# Clock.net
KiCad netlist of a schematic drawn in EAGLE
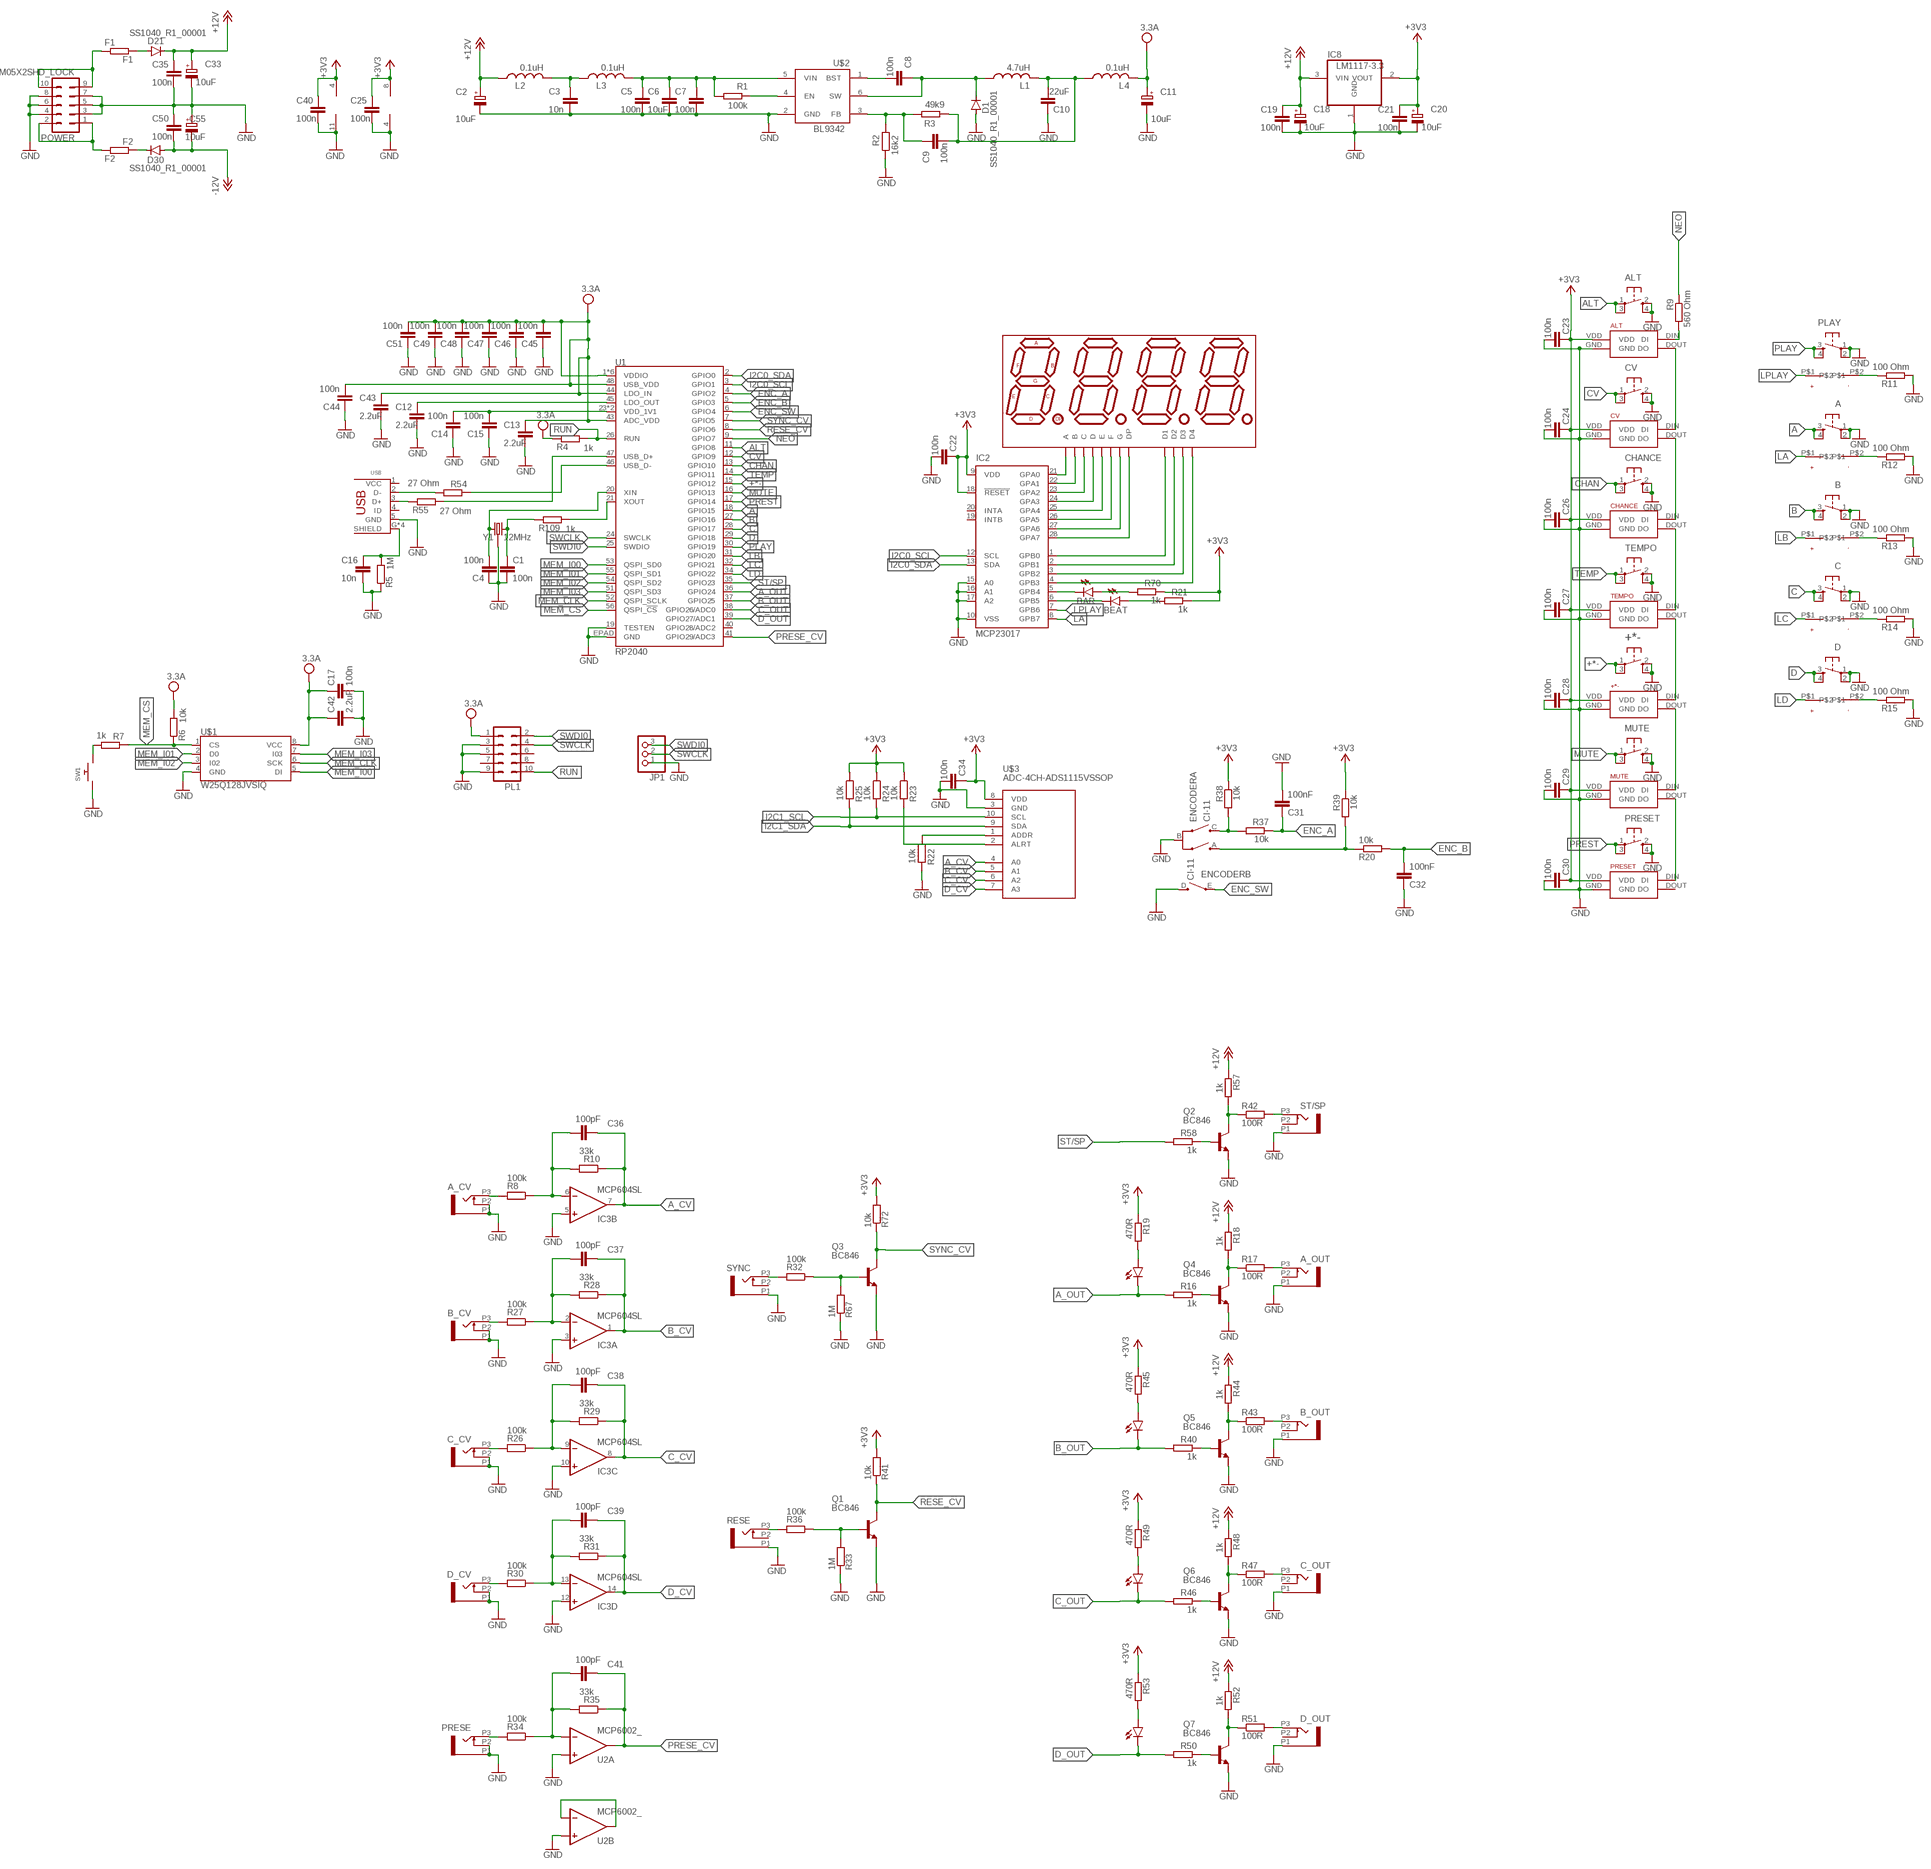
[diagram p0: schematic, sheet 1]

(export (version "E")
  (design (tool "Eeschema 10.0.6"))
  (components
    (comp (ref "+*-")
      (value "BUTTON_NEOPIXEL")
      (footprint "eagle-import:BUTTON_PIXEL")
      (libsource (lib "eagle-import") (part "BUTTON_NEOPIXEL"))
    )
    (comp (ref "A")
      (value "DTS-6_LEDTME")
      (footprint "eagle-import:TMEBUTTON")
      (libsource (lib "eagle-import") (part "DTS-6_LEDTME"))
    )
    (comp (ref "ALT")
      (value "BUTTON_NEOPIXEL")
      (footprint "eagle-import:BUTTON_PIXEL")
      (libsource (lib "eagle-import") (part "BUTTON_NEOPIXEL"))
    )
    (comp (ref "A_CV")
      (value "OG-PJ301_PJ301_THONKICONNNOHOLER")
      (footprint "eagle-import:NOHOLER_GND_SHORT_PADMINI_GND")
      (libsource (lib "eagle-import") (part "OG-PJ301_PJ301_THONKICONNNOHOLER_GND_SHORT_PADMINI_GND"))
    )
    (comp (ref "A_OUT")
      (value "OG-PJ301_PJ301_THONKICONNNOHOLER")
      (footprint "eagle-import:NOHOLER_GND_SHORT_PADMINI_GND")
      (libsource (lib "eagle-import") (part "OG-PJ301_PJ301_THONKICONNNOHOLER_GND_SHORT_PADMINI_GND"))
    )
    (comp (ref "B")
      (value "DTS-6_LEDTME")
      (footprint "eagle-import:TMEBUTTON")
      (libsource (lib "eagle-import") (part "DTS-6_LEDTME"))
    )
    (comp (ref "BAR")
      (value "2 MM LED")
      (footprint "eagle-import:LED3MM")
      (libsource (lib "eagle-import") (part "LED3MM"))
    )
    (comp (ref "BEAT")
      (value "2 MM LED")
      (footprint "eagle-import:LED3MM")
      (libsource (lib "eagle-import") (part "LED3MM"))
    )
    (comp (ref "B_CV")
      (value "OG-PJ301_PJ301_THONKICONNNOHOLER")
      (footprint "eagle-import:NOHOLER_GND_SHORT_PADMINI_GND")
      (libsource (lib "eagle-import") (part "OG-PJ301_PJ301_THONKICONNNOHOLER_GND_SHORT_PADMINI_GND"))
    )
    (comp (ref "B_OUT")
      (value "OG-PJ301_PJ301_THONKICONNNOHOLER")
      (footprint "eagle-import:NOHOLER_GND_SHORT_PADMINI_GND")
      (libsource (lib "eagle-import") (part "OG-PJ301_PJ301_THONKICONNNOHOLER_GND_SHORT_PADMINI_GND"))
    )
    (comp (ref "C")
      (value "DTS-6_LEDTME")
      (footprint "eagle-import:TMEBUTTON")
      (libsource (lib "eagle-import") (part "DTS-6_LEDTME"))
    )
    (comp (ref "C1")
      (value "100n")
      (footprint "eagle-import:C0603")
      (libsource (lib "eagle-import") (part "C-EUC0603"))
    )
    (comp (ref "C2")
      (value "10uF")
      (footprint "eagle-import:PANASONIC_B")
      (libsource (lib "eagle-import") (part "CPOL-EUB"))
    )
    (comp (ref "C3")
      (value "10n")
      (footprint "eagle-import:C0603")
      (libsource (lib "eagle-import") (part "C-EUC0603"))
    )
    (comp (ref "C4")
      (value "100n")
      (footprint "eagle-import:C0603")
      (libsource (lib "eagle-import") (part "C-EUC0603"))
    )
    (comp (ref "C5")
      (value "100n")
      (footprint "eagle-import:C0603")
      (libsource (lib "eagle-import") (part "C-EUC0603"))
    )
    (comp (ref "C6")
      (value "10uF")
      (footprint "eagle-import:C0603")
      (libsource (lib "eagle-import") (part "C-EUC0603"))
    )
    (comp (ref "C7")
      (value "100n")
      (footprint "eagle-import:C0603")
      (libsource (lib "eagle-import") (part "C-EUC0603"))
    )
    (comp (ref "C8")
      (value "100n")
      (footprint "eagle-import:C0603")
      (libsource (lib "eagle-import") (part "C-EUC0603"))
    )
    (comp (ref "C9")
      (value "100n")
      (footprint "eagle-import:C0603")
      (libsource (lib "eagle-import") (part "C-EUC0603"))
    )
    (comp (ref "C10")
      (value "22uF")
      (footprint "eagle-import:C0603")
      (libsource (lib "eagle-import") (part "C-EUC0603"))
    )
    (comp (ref "C11")
      (value "10uF")
      (footprint "eagle-import:PANASONIC_B")
      (libsource (lib "eagle-import") (part "CPOL-EUB"))
    )
    (comp (ref "C12")
      (value "2.2uF")
      (footprint "eagle-import:C0603")
      (libsource (lib "eagle-import") (part "C-EUC0603"))
    )
    (comp (ref "C13")
      (value "2.2uF")
      (footprint "eagle-import:C0603")
      (libsource (lib "eagle-import") (part "C-EUC0603"))
    )
    (comp (ref "C14")
      (value "100n")
      (footprint "eagle-import:C0603")
      (libsource (lib "eagle-import") (part "C-EUC0603"))
    )
    (comp (ref "C15")
      (value "100n")
      (footprint "eagle-import:C0603")
      (libsource (lib "eagle-import") (part "C-EUC0603"))
    )
    (comp (ref "C16")
      (value "10n")
      (footprint "eagle-import:C0603")
      (libsource (lib "eagle-import") (part "C-EUC0603"))
    )
    (comp (ref "C17")
      (value "100n")
      (footprint "eagle-import:C0603")
      (libsource (lib "eagle-import") (part "C-EUC0603"))
    )
    (comp (ref "C18")
      (value "10uF")
      (footprint "eagle-import:PANASONIC_B")
      (libsource (lib "eagle-import") (part "CPOL-EUB"))
    )
    (comp (ref "C19")
      (value "100n")
      (footprint "eagle-import:C0603")
      (libsource (lib "eagle-import") (part "C-EUC0603"))
    )
    (comp (ref "C20")
      (value "10uF")
      (footprint "eagle-import:PANASONIC_B")
      (libsource (lib "eagle-import") (part "CPOL-EUB"))
    )
    (comp (ref "C21")
      (value "100n")
      (footprint "eagle-import:C0603")
      (libsource (lib "eagle-import") (part "C-EUC0603"))
    )
    (comp (ref "C22")
      (value "100n")
      (footprint "eagle-import:C0603")
      (libsource (lib "eagle-import") (part "C-EUC0603"))
    )
    (comp (ref "C23")
      (value "100n")
      (footprint "eagle-import:C0603")
      (libsource (lib "eagle-import") (part "C-EUC0603"))
    )
    (comp (ref "C24")
      (value "100n")
      (footprint "eagle-import:C0603")
      (libsource (lib "eagle-import") (part "C-EUC0603"))
    )
    (comp (ref "C25")
      (value "100n")
      (footprint "eagle-import:C0603")
      (libsource (lib "eagle-import") (part "C-EUC0603"))
    )
    (comp (ref "C26")
      (value "100n")
      (footprint "eagle-import:C0603")
      (libsource (lib "eagle-import") (part "C-EUC0603"))
    )
    (comp (ref "C27")
      (value "100n")
      (footprint "eagle-import:C0603")
      (libsource (lib "eagle-import") (part "C-EUC0603"))
    )
    (comp (ref "C28")
      (value "100n")
      (footprint "eagle-import:C0603")
      (libsource (lib "eagle-import") (part "C-EUC0603"))
    )
    (comp (ref "C29")
      (value "100n")
      (footprint "eagle-import:C0603")
      (libsource (lib "eagle-import") (part "C-EUC0603"))
    )
    (comp (ref "C30")
      (value "100n")
      (footprint "eagle-import:C0603")
      (libsource (lib "eagle-import") (part "C-EUC0603"))
    )
    (comp (ref "C31")
      (value "100nF")
      (footprint "eagle-import:C0603")
      (libsource (lib "eagle-import") (part "rcl_334_C-EUC0603"))
    )
    (comp (ref "C32")
      (value "100nF")
      (footprint "eagle-import:C0603")
      (libsource (lib "eagle-import") (part "rcl_334_C-EUC0603"))
    )
    (comp (ref "C33")
      (value "10uF")
      (footprint "eagle-import:PANASONIC_B")
      (libsource (lib "eagle-import") (part "CPOL-EUB"))
    )
    (comp (ref "C34")
      (value "100n")
      (footprint "eagle-import:C0603")
      (libsource (lib "eagle-import") (part "C-EUC0603"))
    )
    (comp (ref "C35")
      (value "100n")
      (footprint "eagle-import:C0603")
      (libsource (lib "eagle-import") (part "C-EUC0603"))
    )
    (comp (ref "C36")
      (value "100pF")
      (footprint "eagle-import:C0603")
      (libsource (lib "eagle-import") (part "rcl_334_C-EUC0603"))
    )
    (comp (ref "C37")
      (value "100pF")
      (footprint "eagle-import:C0603")
      (libsource (lib "eagle-import") (part "rcl_334_C-EUC0603"))
    )
    (comp (ref "C38")
      (value "100pF")
      (footprint "eagle-import:C0603")
      (libsource (lib "eagle-import") (part "rcl_334_C-EUC0603"))
    )
    (comp (ref "C39")
      (value "100pF")
      (footprint "eagle-import:C0603")
      (libsource (lib "eagle-import") (part "rcl_334_C-EUC0603"))
    )
    (comp (ref "C40")
      (value "100n")
      (footprint "eagle-import:C0603")
      (libsource (lib "eagle-import") (part "C-EUC0603"))
    )
    (comp (ref "C41")
      (value "100pF")
      (footprint "eagle-import:C0603")
      (libsource (lib "eagle-import") (part "rcl_334_C-EUC0603"))
    )
    (comp (ref "C42")
      (value "2.2uF")
      (footprint "eagle-import:C0603")
      (libsource (lib "eagle-import") (part "C-EUC0603"))
    )
    (comp (ref "C43")
      (value "2.2uF")
      (footprint "eagle-import:C0603")
      (libsource (lib "eagle-import") (part "C-EUC0603"))
    )
    (comp (ref "C44")
      (value "100n")
      (footprint "eagle-import:C0603")
      (libsource (lib "eagle-import") (part "C-EUC0603"))
    )
    (comp (ref "C45")
      (value "100n")
      (footprint "eagle-import:C0603")
      (libsource (lib "eagle-import") (part "C-EUC0603"))
    )
    (comp (ref "C46")
      (value "100n")
      (footprint "eagle-import:C0603")
      (libsource (lib "eagle-import") (part "C-EUC0603"))
    )
    (comp (ref "C47")
      (value "100n")
      (footprint "eagle-import:C0603")
      (libsource (lib "eagle-import") (part "C-EUC0603"))
    )
    (comp (ref "C48")
      (value "100n")
      (footprint "eagle-import:C0603")
      (libsource (lib "eagle-import") (part "C-EUC0603"))
    )
    (comp (ref "C49")
      (value "100n")
      (footprint "eagle-import:C0603")
      (libsource (lib "eagle-import") (part "C-EUC0603"))
    )
    (comp (ref "C50")
      (value "100n")
      (footprint "eagle-import:C0603")
      (libsource (lib "eagle-import") (part "C-EUC0603"))
    )
    (comp (ref "C51")
      (value "100n")
      (footprint "eagle-import:C0603")
      (libsource (lib "eagle-import") (part "C-EUC0603"))
    )
    (comp (ref "C55")
      (value "10uF")
      (footprint "eagle-import:PANASONIC_B")
      (libsource (lib "eagle-import") (part "CPOL-EUB"))
    )
    (comp (ref "CHANCE")
      (value "BUTTON_NEOPIXEL")
      (footprint "eagle-import:BUTTON_PIXEL")
      (libsource (lib "eagle-import") (part "BUTTON_NEOPIXEL"))
    )
    (comp (ref "CV")
      (value "BUTTON_NEOPIXEL")
      (footprint "eagle-import:BUTTON_PIXEL")
      (libsource (lib "eagle-import") (part "BUTTON_NEOPIXEL"))
    )
    (comp (ref "C_CV")
      (value "OG-PJ301_PJ301_THONKICONNNOHOLER")
      (footprint "eagle-import:NOHOLER_GND_SHORT_PADMINI_GND")
      (libsource (lib "eagle-import") (part "OG-PJ301_PJ301_THONKICONNNOHOLER_GND_SHORT_PADMINI_GND"))
    )
    (comp (ref "C_OUT")
      (value "OG-PJ301_PJ301_THONKICONNNOHOLER")
      (footprint "eagle-import:NOHOLER_GND_SHORT_PADMINI_GND")
      (libsource (lib "eagle-import") (part "OG-PJ301_PJ301_THONKICONNNOHOLER_GND_SHORT_PADMINI_GND"))
    )
    (comp (ref "D")
      (value "DTS-6_LEDTME")
      (footprint "eagle-import:TMEBUTTON")
      (libsource (lib "eagle-import") (part "DTS-6_LEDTME"))
    )
    (comp (ref "D1")
      (value "SS1040_R1_00001")
      (footprint "eagle-import:SOD123")
      (libsource (lib "eagle-import") (part "DIODE-SOD123"))
    )
    (comp (ref "D21")
      (value "SS1040_R1_00001")
      (footprint "eagle-import:SOD123")
      (libsource (lib "eagle-import") (part "DIODE-SOD123"))
    )
    (comp (ref "D30")
      (value "SS1040_R1_00001")
      (footprint "eagle-import:SOD123")
      (libsource (lib "eagle-import") (part "DIODE-SOD123"))
    )
    (comp (ref "D_CV")
      (value "OG-PJ301_PJ301_THONKICONNNOHOLER")
      (footprint "eagle-import:NOHOLER_GND_SHORT_PADMINI_GND")
      (libsource (lib "eagle-import") (part "OG-PJ301_PJ301_THONKICONNNOHOLER_GND_SHORT_PADMINI_GND"))
    )
    (comp (ref "D_OUT")
      (value "OG-PJ301_PJ301_THONKICONNNOHOLER")
      (footprint "eagle-import:NOHOLER_GND_SHORT_PADMINI_GND")
      (libsource (lib "eagle-import") (part "OG-PJ301_PJ301_THONKICONNNOHOLER_GND_SHORT_PADMINI_GND"))
    )
    (comp (ref "ENCODER")
      (value "CI-11")
      (footprint "eagle-import:CI-11")
      (libsource (lib "eagle-import") (part "CI-11"))
    )
    (comp (ref "F1")
      (value "F1")
      (footprint "eagle-import:R0603")
      (libsource (lib "eagle-import") (part "R-EU_R0603"))
    )
    (comp (ref "F2")
      (value "F2")
      (footprint "eagle-import:R0603")
      (libsource (lib "eagle-import") (part "R-EU_R0603"))
    )
    (comp (ref "IC2")
      (value "MCP23017")
      (footprint "eagle-import:SO28")
      (libsource (lib "eagle-import") (part "MCP23017"))
    )
    (comp (ref "IC3")
      (value "MCP604SL")
      (footprint "eagle-import:SO14")
      (libsource (lib "eagle-import") (part "MCP604SL"))
    )
    (comp (ref "IC8")
      (value "LM1117-3.3")
      (footprint "eagle-import:SOT223")
      (libsource (lib "eagle-import") (part "REG1117"))
    )
    (comp (ref "JP1")
      (value "PINHD-1X31X3*")
      (footprint "eagle-import:1X3_")
      (libsource (lib "eagle-import") (part "PINHD-1X31X3"))
    )
    (comp (ref "L1")
      (value "4.7uH")
      (footprint "eagle-import:L3225P")
      (libsource (lib "eagle-import") (part "L-USL3225P"))
    )
    (comp (ref "L2")
      (value "0.1uH")
      (footprint "eagle-import:L3225P")
      (libsource (lib "eagle-import") (part "L-USL3225P"))
    )
    (comp (ref "L3")
      (value "0.1uH")
      (footprint "eagle-import:L3225P")
      (libsource (lib "eagle-import") (part "L-USL3225P"))
    )
    (comp (ref "L4")
      (value "0.1uH")
      (footprint "eagle-import:L3225P")
      (libsource (lib "eagle-import") (part "L-USL3225P"))
    )
    (comp (ref "LED_A_OUT")
      (value "2 MM LED")
      (footprint "eagle-import:LED3MM")
      (libsource (lib "eagle-import") (part "LED3MM"))
    )
    (comp (ref "LED_B_OUT")
      (value "2 MM LED")
      (footprint "eagle-import:LED3MM")
      (libsource (lib "eagle-import") (part "LED3MM"))
    )
    (comp (ref "LED_C_OUT")
      (value "2 MM LED")
      (footprint "eagle-import:LED3MM")
      (libsource (lib "eagle-import") (part "LED3MM"))
    )
    (comp (ref "LED_D_OUT")
      (value "2 MM LED")
      (footprint "eagle-import:LED3MM")
      (libsource (lib "eagle-import") (part "LED3MM"))
    )
    (comp (ref "LFD36BUE-101B")
      (value "7-SEGMENT-4DIGIT-20MM")
      (footprint "eagle-import:7-SEGMENT-4DIGIT-30MM")
      (libsource (lib "eagle-import") (part "7-SEGMENT-4DIGIT-20MM"))
    )
    (comp (ref "MUTE")
      (value "BUTTON_NEOPIXEL")
      (footprint "eagle-import:BUTTON_PIXEL")
      (libsource (lib "eagle-import") (part "BUTTON_NEOPIXEL"))
    )
    (comp (ref "PL1")
      (value "2X5-1241050")
      (footprint "eagle-import:AMP-1241050-5")
      (libsource (lib "eagle-import") (part "2X5-1241050"))
    )
    (comp (ref "PLAY")
      (value "DTS-6_LEDTME")
      (footprint "eagle-import:TMEBUTTON")
      (libsource (lib "eagle-import") (part "DTS-6_LEDTME"))
    )
    (comp (ref "POWER")
      (value "M05X2SHD_LOCK")
      (footprint "eagle-import:2X5-SHROUDED_LOCK")
      (libsource (lib "eagle-import") (part "M05X2SHD_LOCK"))
    )
    (comp (ref "PRESE")
      (value "OG-PJ301_PJ301_THONKICONNNOHOLER")
      (footprint "eagle-import:NOHOLER_GND_SHORT_PADMINI_GND")
      (libsource (lib "eagle-import") (part "OG-PJ301_PJ301_THONKICONNNOHOLER_GND_SHORT_PADMINI_GND"))
    )
    (comp (ref "PRESET")
      (value "BUTTON_NEOPIXEL")
      (footprint "eagle-import:BUTTON_PIXEL")
      (libsource (lib "eagle-import") (part "BUTTON_NEOPIXEL"))
    )
    (comp (ref "Q1")
      (value "BC846")
      (footprint "eagle-import:SOT23")
      (libsource (lib "eagle-import") (part "BC846"))
    )
    (comp (ref "Q2")
      (value "BC846")
      (footprint "eagle-import:SOT23")
      (libsource (lib "eagle-import") (part "BC846"))
    )
    (comp (ref "Q3")
      (value "BC846")
      (footprint "eagle-import:SOT23")
      (libsource (lib "eagle-import") (part "BC846"))
    )
    (comp (ref "Q4")
      (value "BC846")
      (footprint "eagle-import:SOT23")
      (libsource (lib "eagle-import") (part "BC846"))
    )
    (comp (ref "Q5")
      (value "BC846")
      (footprint "eagle-import:SOT23")
      (libsource (lib "eagle-import") (part "BC846"))
    )
    (comp (ref "Q6")
      (value "BC846")
      (footprint "eagle-import:SOT23")
      (libsource (lib "eagle-import") (part "BC846"))
    )
    (comp (ref "Q7")
      (value "BC846")
      (footprint "eagle-import:SOT23")
      (libsource (lib "eagle-import") (part "BC846"))
    )
    (comp (ref "R1")
      (value "100k")
      (footprint "eagle-import:R0603")
      (libsource (lib "eagle-import") (part "R-EU_R0603"))
    )
    (comp (ref "R2")
      (value "16k2")
      (footprint "eagle-import:R0603")
      (libsource (lib "eagle-import") (part "R-EU_R0603"))
    )
    (comp (ref "R3")
      (value "49k9")
      (footprint "eagle-import:R0603")
      (libsource (lib "eagle-import") (part "R-EU_R0603"))
    )
    (comp (ref "R4")
      (value "1k")
      (footprint "eagle-import:R0603")
      (libsource (lib "eagle-import") (part "R-EU_R0603"))
    )
    (comp (ref "R5")
      (value "1M")
      (footprint "eagle-import:R0603")
      (libsource (lib "eagle-import") (part "R-EU_R0603"))
    )
    (comp (ref "R6")
      (value "10k")
      (footprint "eagle-import:R0603")
      (libsource (lib "eagle-import") (part "R-EU_R0603"))
    )
    (comp (ref "R7")
      (value "1k")
      (footprint "eagle-import:R0603")
      (libsource (lib "eagle-import") (part "R-EU_R0603"))
    )
    (comp (ref "R8")
      (value "100k")
      (footprint "eagle-import:R0603")
      (libsource (lib "eagle-import") (part "R-EU_R0603"))
    )
    (comp (ref "R9")
      (value "560 Ohm")
      (footprint "eagle-import:R0603")
      (libsource (lib "eagle-import") (part "R-EU_R0603"))
    )
    (comp (ref "R10")
      (value "33k")
      (footprint "eagle-import:R0603")
      (libsource (lib "eagle-import") (part "R-EU_R0603"))
    )
    (comp (ref "R11")
      (value "100 Ohm")
      (footprint "eagle-import:R0603")
      (libsource (lib "eagle-import") (part "R-EU_R0603"))
    )
    (comp (ref "R12")
      (value "100 Ohm")
      (footprint "eagle-import:R0603")
      (libsource (lib "eagle-import") (part "R-EU_R0603"))
    )
    (comp (ref "R13")
      (value "100 Ohm")
      (footprint "eagle-import:R0603")
      (libsource (lib "eagle-import") (part "R-EU_R0603"))
    )
    (comp (ref "R14")
      (value "100 Ohm")
      (footprint "eagle-import:R0603")
      (libsource (lib "eagle-import") (part "R-EU_R0603"))
    )
    (comp (ref "R15")
      (value "100 Ohm")
      (footprint "eagle-import:R0603")
      (libsource (lib "eagle-import") (part "R-EU_R0603"))
    )
    (comp (ref "R16")
      (value "1k")
      (footprint "eagle-import:R0603")
      (libsource (lib "eagle-import") (part "R-EU_R0603"))
    )
    (comp (ref "R17")
      (value "100R")
      (footprint "eagle-import:R0603")
      (libsource (lib "eagle-import") (part "R-EU_R0603"))
    )
    (comp (ref "R18")
      (value "1k")
      (footprint "eagle-import:R0603")
      (libsource (lib "eagle-import") (part "R-EU_R0603"))
    )
    (comp (ref "R19")
      (value "470R")
      (footprint "eagle-import:R0603")
      (libsource (lib "eagle-import") (part "R-EU_R0603"))
    )
    (comp (ref "R20")
      (value "10k")
      (footprint "eagle-import:R0603")
      (libsource (lib "eagle-import") (part "rcl_334_R-EU_R0603"))
    )
    (comp (ref "R21")
      (value "1k")
      (footprint "eagle-import:R0603")
      (libsource (lib "eagle-import") (part "R-EU_R0603"))
    )
    (comp (ref "R22")
      (value "10k")
      (footprint "eagle-import:R0603")
      (libsource (lib "eagle-import") (part "R-EU_R0603"))
    )
    (comp (ref "R23")
      (value "10k")
      (footprint "eagle-import:R0603")
      (libsource (lib "eagle-import") (part "R-EU_R0603"))
    )
    (comp (ref "R24")
      (value "10k")
      (footprint "eagle-import:R0603")
      (libsource (lib "eagle-import") (part "R-EU_R0603"))
    )
    (comp (ref "R25")
      (value "10k")
      (footprint "eagle-import:R0603")
      (libsource (lib "eagle-import") (part "R-EU_R0603"))
    )
    (comp (ref "R26")
      (value "100k")
      (footprint "eagle-import:R0603")
      (libsource (lib "eagle-import") (part "R-EU_R0603"))
    )
    (comp (ref "R27")
      (value "100k")
      (footprint "eagle-import:R0603")
      (libsource (lib "eagle-import") (part "R-EU_R0603"))
    )
    (comp (ref "R28")
      (value "33k")
      (footprint "eagle-import:R0603")
      (libsource (lib "eagle-import") (part "R-EU_R0603"))
    )
    (comp (ref "R29")
      (value "33k")
      (footprint "eagle-import:R0603")
      (libsource (lib "eagle-import") (part "R-EU_R0603"))
    )
    (comp (ref "R30")
      (value "100k")
      (footprint "eagle-import:R0603")
      (libsource (lib "eagle-import") (part "R-EU_R0603"))
    )
    (comp (ref "R31")
      (value "33k")
      (footprint "eagle-import:R0603")
      (libsource (lib "eagle-import") (part "R-EU_R0603"))
    )
    (comp (ref "R32")
      (value "100k")
      (footprint "eagle-import:R0603")
      (libsource (lib "eagle-import") (part "R-EU_R0603"))
    )
    (comp (ref "R33")
      (value "1M")
      (footprint "eagle-import:R0603")
      (libsource (lib "eagle-import") (part "R-EU_R0603"))
    )
    (comp (ref "R34")
      (value "100k")
      (footprint "eagle-import:R0603")
      (libsource (lib "eagle-import") (part "R-EU_R0603"))
    )
    (comp (ref "R35")
      (value "33k")
      (footprint "eagle-import:R0603")
      (libsource (lib "eagle-import") (part "R-EU_R0603"))
    )
    (comp (ref "R36")
      (value "100k")
      (footprint "eagle-import:R0603")
      (libsource (lib "eagle-import") (part "R-EU_R0603"))
    )
    (comp (ref "R37")
      (value "10k")
      (footprint "eagle-import:R0603")
      (libsource (lib "eagle-import") (part "rcl_334_R-EU_R0603"))
    )
    (comp (ref "R38")
      (value "10k")
      (footprint "eagle-import:R0603")
      (libsource (lib "eagle-import") (part "rcl_334_R-EU_R0603"))
    )
    (comp (ref "R39")
      (value "10k")
      (footprint "eagle-import:R0603")
      (libsource (lib "eagle-import") (part "rcl_334_R-EU_R0603"))
    )
    (comp (ref "R40")
      (value "1k")
      (footprint "eagle-import:R0603")
      (libsource (lib "eagle-import") (part "R-EU_R0603"))
    )
    (comp (ref "R41")
      (value "10k")
      (footprint "eagle-import:R0603")
      (libsource (lib "eagle-import") (part "R-EU_R0603"))
    )
    (comp (ref "R42")
      (value "100R")
      (footprint "eagle-import:R0603")
      (libsource (lib "eagle-import") (part "R-EU_R0603"))
    )
    (comp (ref "R43")
      (value "100R")
      (footprint "eagle-import:R0603")
      (libsource (lib "eagle-import") (part "R-EU_R0603"))
    )
    (comp (ref "R44")
      (value "1k")
      (footprint "eagle-import:R0603")
      (libsource (lib "eagle-import") (part "R-EU_R0603"))
    )
    (comp (ref "R45")
      (value "470R")
      (footprint "eagle-import:R0603")
      (libsource (lib "eagle-import") (part "R-EU_R0603"))
    )
    (comp (ref "R46")
      (value "1k")
      (footprint "eagle-import:R0603")
      (libsource (lib "eagle-import") (part "R-EU_R0603"))
    )
    (comp (ref "R47")
      (value "100R")
      (footprint "eagle-import:R0603")
      (libsource (lib "eagle-import") (part "R-EU_R0603"))
    )
    (comp (ref "R48")
      (value "1k")
      (footprint "eagle-import:R0603")
      (libsource (lib "eagle-import") (part "R-EU_R0603"))
    )
    (comp (ref "R49")
      (value "470R")
      (footprint "eagle-import:R0603")
      (libsource (lib "eagle-import") (part "R-EU_R0603"))
    )
    (comp (ref "R50")
      (value "1k")
      (footprint "eagle-import:R0603")
      (libsource (lib "eagle-import") (part "R-EU_R0603"))
    )
    (comp (ref "R51")
      (value "100R")
      (footprint "eagle-import:R0603")
      (libsource (lib "eagle-import") (part "R-EU_R0603"))
    )
    (comp (ref "R52")
      (value "1k")
      (footprint "eagle-import:R0603")
      (libsource (lib "eagle-import") (part "R-EU_R0603"))
    )
    (comp (ref "R53")
      (value "470R")
      (footprint "eagle-import:R0603")
      (libsource (lib "eagle-import") (part "R-EU_R0603"))
    )
    (comp (ref "R54")
      (value "27 Ohm")
      (footprint "eagle-import:R0603")
      (libsource (lib "eagle-import") (part "R-EU_R0603"))
    )
    (comp (ref "R55")
      (value "27 Ohm")
      (footprint "eagle-import:R0603")
      (libsource (lib "eagle-import") (part "R-EU_R0603"))
    )
    (comp (ref "R57")
      (value "1k")
      (footprint "eagle-import:R0603")
      (libsource (lib "eagle-import") (part "R-EU_R0603"))
    )
    (comp (ref "R58")
      (value "1k")
      (footprint "eagle-import:R0603")
      (libsource (lib "eagle-import") (part "R-EU_R0603"))
    )
    (comp (ref "R67")
      (value "1M")
      (footprint "eagle-import:R0603")
      (libsource (lib "eagle-import") (part "R-EU_R0603"))
    )
    (comp (ref "R70")
      (value "1k")
      (footprint "eagle-import:R0603")
      (libsource (lib "eagle-import") (part "R-EU_R0603"))
    )
    (comp (ref "R72")
      (value "10k")
      (footprint "eagle-import:R0603")
      (libsource (lib "eagle-import") (part "R-EU_R0603"))
    )
    (comp (ref "R109")
      (value "1k")
      (footprint "eagle-import:R0603")
      (libsource (lib "eagle-import") (part "R-EU_R0603"))
    )
    (comp (ref "RESE")
      (value "OG-PJ301_PJ301_THONKICONNNOHOLER")
      (footprint "eagle-import:NOHOLER_GND_SHORT_PADMINI_GND")
      (libsource (lib "eagle-import") (part "OG-PJ301_PJ301_THONKICONNNOHOLER_GND_SHORT_PADMINI_GND"))
    )
    (comp (ref "ST/SP")
      (value "OG-PJ301_PJ301_THONKICONNNOHOLER")
      (footprint "eagle-import:NOHOLER_GND_SHORT_PADMINI_GND")
      (libsource (lib "eagle-import") (part "OG-PJ301_PJ301_THONKICONNNOHOLER_GND_SHORT_PADMINI_GND"))
    )
    (comp (ref "SW1")
      (value "SWITCH_PUSHBUTTONSOFTTOUCHSMD_SJ")
      (footprint "eagle-import:PUSHBUTTON_SMD_SJ")
      (libsource (lib "eagle-import") (part "SWITCH_PUSHBUTTONSOFTTOUCHSMD_SJ"))
    )
    (comp (ref "SYNC")
      (value "OG-PJ301_PJ301_THONKICONNNOHOLER")
      (footprint "eagle-import:NOHOLER_GND_SHORT_PADMINI_GND")
      (libsource (lib "eagle-import") (part "OG-PJ301_PJ301_THONKICONNNOHOLER_GND_SHORT_PADMINI_GND"))
    )
    (comp (ref "TEMPO")
      (value "BUTTON_NEOPIXEL")
      (footprint "eagle-import:BUTTON_PIXEL")
      (libsource (lib "eagle-import") (part "BUTTON_NEOPIXEL"))
    )
    (comp (ref "U$1")
      (value "W25Q128JVSIQ")
      (footprint "eagle-import:SOIC-8")
      (libsource (lib "eagle-import") (part "W25Q128JVSIQ"))
    )
    (comp (ref "U$2")
      (value "BL9342")
      (footprint "eagle-import:SOT23-6")
      (libsource (lib "eagle-import") (part "BL9342"))
    )
    (comp (ref "U$3")
      (value "ADC-4CH-ADS1115VSSOP")
      (footprint "eagle-import:ADC-4CH-ADS1115-VSSOP")
      (libsource (lib "eagle-import") (part "ADC-4CH-ADS1115VSSOP"))
    )
    (comp (ref "U1")
      (value "RP2040")
      (footprint "eagle-import:QFN-56")
      (libsource (lib "eagle-import") (part "RP2040"))
    )
    (comp (ref "U2")
      (value "MCP6002_")
      (footprint "eagle-import:SO08")
      (libsource (lib "eagle-import") (part "MCP6002_"))
    )
    (comp (ref "USB")
      (value "USB_HRS_ZX62-B-5PA(11)MICRO.B")
      (footprint "eagle-import:HRS_ZX62RD-AB-5P8")
      (libsource (lib "eagle-import") (part "USB_HRS_ZX62-B-5PA(11)MICRO.B"))
    )
    (comp (ref "Y1")
      (value "12MHz")
      (footprint "eagle-import:CRYSTAL-SMD-2.0X1.6MM-WE")
      (libsource (lib "eagle-import") (part "CRYSTAL-25MHZ-WE-SMD-2.0X1.6MM-WE"))
    )
  )
  (nets
    (net (code "1") (name "+*-") (class "Default")
      (node (ref "+*-") (pin "1") (pinfunction "1_1") (pintype "passive"))
      (node (ref "+*-") (pin "3") (pinfunction "3_3") (pintype "passive"))
      (node (ref "U1") (pin "15") (pinfunction "GPIO12_15") (pintype "bidirectional"))
    )
    (net (code "2") (name "+3V3") (class "Default")
      (node (ref "+*-") (pin "VDD") (pinfunction "VDD_VDD") (pintype "bidirectional"))
      (node (ref "ALT") (pin "VDD") (pinfunction "VDD_VDD") (pintype "bidirectional"))
      (node (ref "C20") (pin "+") (pinfunction "+_+") (pintype "passive"))
      (node (ref "C21") (pin "1") (pinfunction "1_1") (pintype "passive"))
      (node (ref "C22") (pin "1") (pinfunction "1_1") (pintype "passive"))
      (node (ref "C23") (pin "1") (pinfunction "1_1") (pintype "passive"))
      (node (ref "C24") (pin "1") (pinfunction "1_1") (pintype "passive"))
      (node (ref "C25") (pin "1") (pinfunction "1_1") (pintype "passive"))
      (node (ref "C26") (pin "1") (pinfunction "1_1") (pintype "passive"))
      (node (ref "C27") (pin "1") (pinfunction "1_1") (pintype "passive"))
      (node (ref "C28") (pin "1") (pinfunction "1_1") (pintype "passive"))
      (node (ref "C29") (pin "1") (pinfunction "1_1") (pintype "passive"))
      (node (ref "C30") (pin "1") (pinfunction "1_1") (pintype "passive"))
      (node (ref "C34") (pin "1") (pinfunction "1_1") (pintype "passive"))
      (node (ref "C40") (pin "1") (pinfunction "1_1") (pintype "passive"))
      (node (ref "CHANCE") (pin "VDD") (pinfunction "VDD_VDD") (pintype "bidirectional"))
      (node (ref "CV") (pin "VDD") (pinfunction "VDD_VDD") (pintype "bidirectional"))
      (node (ref "IC2") (pin "18") (pinfunction "~{RESET}_18") (pintype "input"))
      (node (ref "IC2") (pin "9") (pinfunction "VDD_9") (pintype "power_in"))
      (node (ref "IC3") (pin "4") (pinfunction "V+_4") (pintype "power_in"))
      (node (ref "IC8") (pin "2") (pinfunction "VOUT_2") (pintype "output"))
      (node (ref "MUTE") (pin "VDD") (pinfunction "VDD_VDD") (pintype "bidirectional"))
      (node (ref "PRESET") (pin "VDD") (pinfunction "VDD_VDD") (pintype "bidirectional"))
      (node (ref "R19") (pin "1") (pinfunction "1_1") (pintype "passive"))
      (node (ref "R21") (pin "1") (pinfunction "1_1") (pintype "passive"))
      (node (ref "R23") (pin "1") (pinfunction "1_1") (pintype "passive"))
      (node (ref "R24") (pin "1") (pinfunction "1_1") (pintype "passive"))
      (node (ref "R25") (pin "1") (pinfunction "1_1") (pintype "passive"))
      (node (ref "R38") (pin "1") (pinfunction "1_1") (pintype "passive"))
      (node (ref "R39") (pin "1") (pinfunction "1_1") (pintype "passive"))
      (node (ref "R41") (pin "2") (pinfunction "2_2") (pintype "passive"))
      (node (ref "R45") (pin "1") (pinfunction "1_1") (pintype "passive"))
      (node (ref "R49") (pin "1") (pinfunction "1_1") (pintype "passive"))
      (node (ref "R53") (pin "1") (pinfunction "1_1") (pintype "passive"))
      (node (ref "R70") (pin "1") (pinfunction "1_1") (pintype "passive"))
      (node (ref "R72") (pin "2") (pinfunction "2_2") (pintype "passive"))
      (node (ref "TEMPO") (pin "VDD") (pinfunction "VDD_VDD") (pintype "bidirectional"))
      (node (ref "U$3") (pin "8") (pinfunction "VDD_8") (pintype "power_in"))
      (node (ref "U2") (pin "8") (pinfunction "V+_8") (pintype "power_in"))
    )
    (net (code "3") (name "+12V") (class "Default")
      (node (ref "C18") (pin "+") (pinfunction "+_+") (pintype "passive"))
      (node (ref "C19") (pin "1") (pinfunction "1_1") (pintype "passive"))
      (node (ref "C2") (pin "+") (pinfunction "+_+") (pintype "passive"))
      (node (ref "C33") (pin "+") (pinfunction "+_+") (pintype "passive"))
      (node (ref "C35") (pin "1") (pinfunction "1_1") (pintype "passive"))
      (node (ref "D21") (pin "C") (pinfunction "C_C") (pintype "passive"))
      (node (ref "IC8") (pin "3") (pinfunction "VIN_3") (pintype "input"))
      (node (ref "L2") (pin "1") (pinfunction "1_1") (pintype "passive"))
      (node (ref "R18") (pin "1") (pinfunction "1_1") (pintype "passive"))
      (node (ref "R44") (pin "1") (pinfunction "1_1") (pintype "passive"))
      (node (ref "R48") (pin "1") (pinfunction "1_1") (pintype "passive"))
      (node (ref "R52") (pin "1") (pinfunction "1_1") (pintype "passive"))
      (node (ref "R57") (pin "1") (pinfunction "1_1") (pintype "passive"))
    )
    (net (code "4") (name "-12V") (class "Default")
      (node (ref "C50") (pin "2") (pinfunction "2_2") (pintype "passive"))
      (node (ref "C55") (pin "-") (pinfunction "-_-") (pintype "passive"))
      (node (ref "D30") (pin "A") (pinfunction "A_A") (pintype "passive"))
    )
    (net (code "5") (name "3.3A") (class "Default")
      (node (ref "C11") (pin "+") (pinfunction "+_+") (pintype "passive"))
      (node (ref "C13") (pin "1") (pinfunction "1_1") (pintype "passive"))
      (node (ref "C17") (pin "1") (pinfunction "1_1") (pintype "passive"))
      (node (ref "C42") (pin "1") (pinfunction "1_1") (pintype "passive"))
      (node (ref "C43") (pin "1") (pinfunction "1_1") (pintype "passive"))
      (node (ref "C44") (pin "2") (pinfunction "2_2") (pintype "passive"))
      (node (ref "C45") (pin "2") (pinfunction "2_2") (pintype "passive"))
      (node (ref "C46") (pin "2") (pinfunction "2_2") (pintype "passive"))
      (node (ref "C47") (pin "2") (pinfunction "2_2") (pintype "passive"))
      (node (ref "C48") (pin "2") (pinfunction "2_2") (pintype "passive"))
      (node (ref "C49") (pin "2") (pinfunction "2_2") (pintype "passive"))
      (node (ref "C51") (pin "2") (pinfunction "2_2") (pintype "passive"))
      (node (ref "L4") (pin "2") (pinfunction "2_2") (pintype "passive"))
      (node (ref "PL1") (pin "1") (pinfunction "1_1") (pintype "passive"))
      (node (ref "R4") (pin "1") (pinfunction "1_1") (pintype "passive"))
      (node (ref "R6") (pin "2") (pinfunction "2_2") (pintype "passive"))
      (node (ref "U$1") (pin "8") (pinfunction "VCC_8") (pintype "bidirectional"))
      (node (ref "U1") (pin "1") (pinfunction "VDDIO_1") (pintype "bidirectional"))
      (node (ref "U1") (pin "10") (pinfunction "VDDIO_10") (pintype "bidirectional"))
      (node (ref "U1") (pin "22") (pinfunction "VDDIO_22") (pintype "bidirectional"))
      (node (ref "U1") (pin "33") (pinfunction "VDDIO_33") (pintype "bidirectional"))
      (node (ref "U1") (pin "42") (pinfunction "VDDIO_42") (pintype "bidirectional"))
      (node (ref "U1") (pin "43") (pinfunction "ADC_VDD_43") (pintype "bidirectional"))
      (node (ref "U1") (pin "44") (pinfunction "LDO_IN_44") (pintype "bidirectional"))
      (node (ref "U1") (pin "48") (pinfunction "USB_VDD_48") (pintype "bidirectional"))
      (node (ref "U1") (pin "49") (pinfunction "VDDIO_49") (pintype "bidirectional"))
    )
    (net (code "6") (name "A") (class "Default")
      (node (ref "A") (pin "3") (pinfunction "3_3") (pintype "passive"))
      (node (ref "A") (pin "4") (pinfunction "4_4") (pintype "passive"))
      (node (ref "U1") (pin "18") (pinfunction "GPIO15_18") (pintype "bidirectional"))
    )
    (net (code "7") (name "ALT") (class "Default")
      (node (ref "ALT") (pin "1") (pinfunction "1_1") (pintype "passive"))
      (node (ref "ALT") (pin "3") (pinfunction "3_3") (pintype "passive"))
      (node (ref "U1") (pin "11") (pinfunction "GPIO8_11") (pintype "bidirectional"))
    )
    (net (code "8") (name "A_CV") (class "Default")
      (node (ref "C36") (pin "2") (pinfunction "2_2") (pintype "passive"))
      (node (ref "IC3") (pin "7") (pinfunction "OUT_7") (pintype "output"))
      (node (ref "R10") (pin "1") (pinfunction "1_1") (pintype "passive"))
      (node (ref "U$3") (pin "4") (pinfunction "A0_4") (pintype "input"))
    )
    (net (code "9") (name "A_OUT") (class "Default")
      (node (ref "LED_A_OUT") (pin "K") (pinfunction "C_K") (pintype "passive"))
      (node (ref "R16") (pin "2") (pinfunction "2_2") (pintype "passive"))
      (node (ref "U1") (pin "36") (pinfunction "GPIO24_36") (pintype "bidirectional"))
    )
    (net (code "10") (name "B") (class "Default")
      (node (ref "B") (pin "3") (pinfunction "3_3") (pintype "passive"))
      (node (ref "B") (pin "4") (pinfunction "4_4") (pintype "passive"))
      (node (ref "U1") (pin "27") (pinfunction "GPIO16_27") (pintype "bidirectional"))
    )
    (net (code "11") (name "B_CV") (class "Default")
      (node (ref "C37") (pin "2") (pinfunction "2_2") (pintype "passive"))
      (node (ref "IC3") (pin "1") (pinfunction "OUT_1") (pintype "output"))
      (node (ref "R28") (pin "1") (pinfunction "1_1") (pintype "passive"))
      (node (ref "U$3") (pin "5") (pinfunction "A1_5") (pintype "input"))
    )
    (net (code "12") (name "B_OUT") (class "Default")
      (node (ref "LED_B_OUT") (pin "K") (pinfunction "C_K") (pintype "passive"))
      (node (ref "R40") (pin "2") (pinfunction "2_2") (pintype "passive"))
      (node (ref "U1") (pin "37") (pinfunction "GPIO25_37") (pintype "bidirectional"))
    )
    (net (code "13") (name "C") (class "Default")
      (node (ref "C") (pin "3") (pinfunction "3_3") (pintype "passive"))
      (node (ref "C") (pin "4") (pinfunction "4_4") (pintype "passive"))
      (node (ref "U1") (pin "28") (pinfunction "GPIO17_28") (pintype "bidirectional"))
    )
    (net (code "14") (name "CHAN") (class "Default")
      (node (ref "CHANCE") (pin "1") (pinfunction "1_1") (pintype "passive"))
      (node (ref "CHANCE") (pin "3") (pinfunction "3_3") (pintype "passive"))
      (node (ref "U1") (pin "13") (pinfunction "GPIO10_13") (pintype "bidirectional"))
    )
    (net (code "15") (name "CV") (class "Default")
      (node (ref "CV") (pin "1") (pinfunction "1_1") (pintype "passive"))
      (node (ref "CV") (pin "3") (pinfunction "3_3") (pintype "passive"))
      (node (ref "U1") (pin "12") (pinfunction "GPIO9_12") (pintype "bidirectional"))
    )
    (net (code "16") (name "C_CV") (class "Default")
      (node (ref "C38") (pin "2") (pinfunction "2_2") (pintype "passive"))
      (node (ref "IC3") (pin "8") (pinfunction "OUT_8") (pintype "output"))
      (node (ref "R29") (pin "1") (pinfunction "1_1") (pintype "passive"))
      (node (ref "U$3") (pin "6") (pinfunction "A2_6") (pintype "input"))
    )
    (net (code "17") (name "C_OUT") (class "Default")
      (node (ref "LED_C_OUT") (pin "K") (pinfunction "C_K") (pintype "passive"))
      (node (ref "R46") (pin "2") (pinfunction "2_2") (pintype "passive"))
      (node (ref "U1") (pin "38") (pinfunction "GPIO26/ADC0_38") (pintype "bidirectional"))
    )
    (net (code "18") (name "D") (class "Default")
      (node (ref "D") (pin "3") (pinfunction "3_3") (pintype "passive"))
      (node (ref "D") (pin "4") (pinfunction "4_4") (pintype "passive"))
      (node (ref "U1") (pin "29") (pinfunction "GPIO18_29") (pintype "bidirectional"))
    )
    (net (code "19") (name "D_CV") (class "Default")
      (node (ref "C39") (pin "2") (pinfunction "2_2") (pintype "passive"))
      (node (ref "IC3") (pin "14") (pinfunction "OUT_14") (pintype "output"))
      (node (ref "R31") (pin "1") (pinfunction "1_1") (pintype "passive"))
      (node (ref "U$3") (pin "7") (pinfunction "A3_7") (pintype "input"))
    )
    (net (code "20") (name "D_OUT") (class "Default")
      (node (ref "LED_D_OUT") (pin "K") (pinfunction "C_K") (pintype "passive"))
      (node (ref "R50") (pin "2") (pinfunction "2_2") (pintype "passive"))
      (node (ref "U1") (pin "39") (pinfunction "GPIO27/ADC1_39") (pintype "bidirectional"))
    )
    (net (code "21") (name "ENC_A") (class "Default")
      (node (ref "C31") (pin "1") (pinfunction "1_1") (pintype "passive"))
      (node (ref "R37") (pin "1") (pinfunction "1_1") (pintype "passive"))
      (node (ref "U1") (pin "4") (pinfunction "GPIO2_4") (pintype "bidirectional"))
    )
    (net (code "22") (name "ENC_B") (class "Default")
      (node (ref "C32") (pin "2") (pinfunction "2_2") (pintype "passive"))
      (node (ref "R20") (pin "2") (pinfunction "2_2") (pintype "passive"))
      (node (ref "U1") (pin "5") (pinfunction "GPIO3_5") (pintype "bidirectional"))
    )
    (net (code "23") (name "ENC_SW") (class "Default")
      (node (ref "ENCODER") (pin "E") (pinfunction "E_E") (pintype "passive"))
      (node (ref "U1") (pin "6") (pinfunction "GPIO4_6") (pintype "bidirectional"))
    )
    (net (code "24") (name "GND") (class "Default")
      (node (ref "+*-") (pin "2") (pinfunction "2_2") (pintype "passive"))
      (node (ref "+*-") (pin "4") (pinfunction "4_4") (pintype "passive"))
      (node (ref "+*-") (pin "GND") (pinfunction "GND_GND") (pintype "bidirectional"))
      (node (ref "A") (pin "1") (pinfunction "1_1") (pintype "passive"))
      (node (ref "A") (pin "2") (pinfunction "2_2") (pintype "passive"))
      (node (ref "ALT") (pin "2") (pinfunction "2_2") (pintype "passive"))
      (node (ref "ALT") (pin "4") (pinfunction "4_4") (pintype "passive"))
      (node (ref "ALT") (pin "GND") (pinfunction "GND_GND") (pintype "bidirectional"))
      (node (ref "A_CV") (pin "P1") (pinfunction "1_P1") (pintype "passive"))
      (node (ref "A_CV") (pin "P2") (pinfunction "2_P2") (pintype "passive"))
      (node (ref "A_OUT") (pin "P1") (pinfunction "1_P1") (pintype "passive"))
      (node (ref "B") (pin "1") (pinfunction "1_1") (pintype "passive"))
      (node (ref "B") (pin "2") (pinfunction "2_2") (pintype "passive"))
      (node (ref "B_CV") (pin "P1") (pinfunction "1_P1") (pintype "passive"))
      (node (ref "B_CV") (pin "P2") (pinfunction "2_P2") (pintype "passive"))
      (node (ref "B_OUT") (pin "P1") (pinfunction "1_P1") (pintype "passive"))
      (node (ref "C") (pin "1") (pinfunction "1_1") (pintype "passive"))
      (node (ref "C") (pin "2") (pinfunction "2_2") (pintype "passive"))
      (node (ref "C1") (pin "2") (pinfunction "2_2") (pintype "passive"))
      (node (ref "C10") (pin "1") (pinfunction "1_1") (pintype "passive"))
      (node (ref "C11") (pin "-") (pinfunction "-_-") (pintype "passive"))
      (node (ref "C12") (pin "2") (pinfunction "2_2") (pintype "passive"))
      (node (ref "C13") (pin "2") (pinfunction "2_2") (pintype "passive"))
      (node (ref "C14") (pin "1") (pinfunction "1_1") (pintype "passive"))
      (node (ref "C15") (pin "1") (pinfunction "1_1") (pintype "passive"))
      (node (ref "C16") (pin "2") (pinfunction "2_2") (pintype "passive"))
      (node (ref "C17") (pin "2") (pinfunction "2_2") (pintype "passive"))
      (node (ref "C18") (pin "-") (pinfunction "-_-") (pintype "passive"))
      (node (ref "C19") (pin "2") (pinfunction "2_2") (pintype "passive"))
      (node (ref "C2") (pin "-") (pinfunction "-_-") (pintype "passive"))
      (node (ref "C20") (pin "-") (pinfunction "-_-") (pintype "passive"))
      (node (ref "C21") (pin "2") (pinfunction "2_2") (pintype "passive"))
      (node (ref "C22") (pin "2") (pinfunction "2_2") (pintype "passive"))
      (node (ref "C23") (pin "2") (pinfunction "2_2") (pintype "passive"))
      (node (ref "C24") (pin "2") (pinfunction "2_2") (pintype "passive"))
      (node (ref "C25") (pin "2") (pinfunction "2_2") (pintype "passive"))
      (node (ref "C26") (pin "2") (pinfunction "2_2") (pintype "passive"))
      (node (ref "C27") (pin "2") (pinfunction "2_2") (pintype "passive"))
      (node (ref "C28") (pin "2") (pinfunction "2_2") (pintype "passive"))
      (node (ref "C29") (pin "2") (pinfunction "2_2") (pintype "passive"))
      (node (ref "C3") (pin "2") (pinfunction "2_2") (pintype "passive"))
      (node (ref "C30") (pin "2") (pinfunction "2_2") (pintype "passive"))
      (node (ref "C31") (pin "2") (pinfunction "2_2") (pintype "passive"))
      (node (ref "C32") (pin "1") (pinfunction "1_1") (pintype "passive"))
      (node (ref "C33") (pin "-") (pinfunction "-_-") (pintype "passive"))
      (node (ref "C34") (pin "2") (pinfunction "2_2") (pintype "passive"))
      (node (ref "C35") (pin "2") (pinfunction "2_2") (pintype "passive"))
      (node (ref "C4") (pin "1") (pinfunction "1_1") (pintype "passive"))
      (node (ref "C40") (pin "2") (pinfunction "2_2") (pintype "passive"))
      (node (ref "C42") (pin "2") (pinfunction "2_2") (pintype "passive"))
      (node (ref "C43") (pin "2") (pinfunction "2_2") (pintype "passive"))
      (node (ref "C44") (pin "1") (pinfunction "1_1") (pintype "passive"))
      (node (ref "C45") (pin "1") (pinfunction "1_1") (pintype "passive"))
      (node (ref "C46") (pin "1") (pinfunction "1_1") (pintype "passive"))
      (node (ref "C47") (pin "1") (pinfunction "1_1") (pintype "passive"))
      (node (ref "C48") (pin "1") (pinfunction "1_1") (pintype "passive"))
      (node (ref "C49") (pin "1") (pinfunction "1_1") (pintype "passive"))
      (node (ref "C5") (pin "2") (pinfunction "2_2") (pintype "passive"))
      (node (ref "C50") (pin "1") (pinfunction "1_1") (pintype "passive"))
      (node (ref "C51") (pin "1") (pinfunction "1_1") (pintype "passive"))
      (node (ref "C55") (pin "+") (pinfunction "+_+") (pintype "passive"))
      (node (ref "C6") (pin "2") (pinfunction "2_2") (pintype "passive"))
      (node (ref "C7") (pin "2") (pinfunction "2_2") (pintype "passive"))
      (node (ref "CHANCE") (pin "2") (pinfunction "2_2") (pintype "passive"))
      (node (ref "CHANCE") (pin "4") (pinfunction "4_4") (pintype "passive"))
      (node (ref "CHANCE") (pin "GND") (pinfunction "GND_GND") (pintype "bidirectional"))
      (node (ref "CV") (pin "2") (pinfunction "2_2") (pintype "passive"))
      (node (ref "CV") (pin "4") (pinfunction "4_4") (pintype "passive"))
      (node (ref "CV") (pin "GND") (pinfunction "GND_GND") (pintype "bidirectional"))
      (node (ref "C_CV") (pin "P1") (pinfunction "1_P1") (pintype "passive"))
      (node (ref "C_CV") (pin "P2") (pinfunction "2_P2") (pintype "passive"))
      (node (ref "C_OUT") (pin "P1") (pinfunction "1_P1") (pintype "passive"))
      (node (ref "D") (pin "1") (pinfunction "1_1") (pintype "passive"))
      (node (ref "D") (pin "2") (pinfunction "2_2") (pintype "passive"))
      (node (ref "D1") (pin "A") (pinfunction "A_A") (pintype "passive"))
      (node (ref "D_CV") (pin "P1") (pinfunction "1_P1") (pintype "passive"))
      (node (ref "D_CV") (pin "P2") (pinfunction "2_P2") (pintype "passive"))
      (node (ref "D_OUT") (pin "P1") (pinfunction "1_P1") (pintype "passive"))
      (node (ref "ENCODER") (pin "B") (pinfunction "C_B") (pintype "passive"))
      (node (ref "ENCODER") (pin "D") (pinfunction "D_D") (pintype "passive"))
      (node (ref "IC2") (pin "10") (pinfunction "VSS_10") (pintype "power_in"))
      (node (ref "IC2") (pin "15") (pinfunction "A0_15") (pintype "input"))
      (node (ref "IC2") (pin "16") (pinfunction "A1_16") (pintype "input"))
      (node (ref "IC2") (pin "17") (pinfunction "A2_17") (pintype "input"))
      (node (ref "IC3") (pin "10") (pinfunction "+IN_10") (pintype "input"))
      (node (ref "IC3") (pin "11") (pinfunction "V-_11") (pintype "power_in"))
      (node (ref "IC3") (pin "12") (pinfunction "+IN_12") (pintype "input"))
      (node (ref "IC3") (pin "3") (pinfunction "+IN_3") (pintype "input"))
      (node (ref "IC3") (pin "5") (pinfunction "+IN_5") (pintype "input"))
      (node (ref "IC8") (pin "1") (pinfunction "GND_1") (pintype "power_in"))
      (node (ref "JP1") (pin "1") (pinfunction "1_1") (pintype "passive"))
      (node (ref "MUTE") (pin "2") (pinfunction "2_2") (pintype "passive"))
      (node (ref "MUTE") (pin "4") (pinfunction "4_4") (pintype "passive"))
      (node (ref "MUTE") (pin "GND") (pinfunction "GND_GND") (pintype "bidirectional"))
      (node (ref "PL1") (pin "3") (pinfunction "3_3") (pintype "passive"))
      (node (ref "PL1") (pin "5") (pinfunction "5_5") (pintype "passive"))
      (node (ref "PL1") (pin "9") (pinfunction "9_9") (pintype "passive"))
      (node (ref "PLAY") (pin "1") (pinfunction "1_1") (pintype "passive"))
      (node (ref "PLAY") (pin "2") (pinfunction "2_2") (pintype "passive"))
      (node (ref "POWER") (pin "3") (pinfunction "3_3") (pintype "passive"))
      (node (ref "POWER") (pin "4") (pinfunction "4_4") (pintype "passive"))
      (node (ref "POWER") (pin "5") (pinfunction "5_5") (pintype "passive"))
      (node (ref "POWER") (pin "6") (pinfunction "6_6") (pintype "passive"))
      (node (ref "POWER") (pin "7") (pinfunction "7_7") (pintype "passive"))
      (node (ref "POWER") (pin "8") (pinfunction "8_8") (pintype "passive"))
      (node (ref "PRESE") (pin "P1") (pinfunction "1_P1") (pintype "passive"))
      (node (ref "PRESE") (pin "P2") (pinfunction "2_P2") (pintype "passive"))
      (node (ref "PRESET") (pin "2") (pinfunction "2_2") (pintype "passive"))
      (node (ref "PRESET") (pin "4") (pinfunction "4_4") (pintype "passive"))
      (node (ref "PRESET") (pin "GND") (pinfunction "GND_GND") (pintype "bidirectional"))
      (node (ref "Q1") (pin "2") (pinfunction "E_2") (pintype "passive"))
      (node (ref "Q2") (pin "2") (pinfunction "E_2") (pintype "passive"))
      (node (ref "Q3") (pin "2") (pinfunction "E_2") (pintype "passive"))
      (node (ref "Q4") (pin "2") (pinfunction "E_2") (pintype "passive"))
      (node (ref "Q5") (pin "2") (pinfunction "E_2") (pintype "passive"))
      (node (ref "Q6") (pin "2") (pinfunction "E_2") (pintype "passive"))
      (node (ref "Q7") (pin "2") (pinfunction "E_2") (pintype "passive"))
      (node (ref "R11") (pin "2") (pinfunction "2_2") (pintype "passive"))
      (node (ref "R12") (pin "2") (pinfunction "2_2") (pintype "passive"))
      (node (ref "R13") (pin "2") (pinfunction "2_2") (pintype "passive"))
      (node (ref "R14") (pin "2") (pinfunction "2_2") (pintype "passive"))
      (node (ref "R15") (pin "2") (pinfunction "2_2") (pintype "passive"))
      (node (ref "R2") (pin "1") (pinfunction "1_1") (pintype "passive"))
      (node (ref "R22") (pin "2") (pinfunction "2_2") (pintype "passive"))
      (node (ref "R33") (pin "1") (pinfunction "1_1") (pintype "passive"))
      (node (ref "R5") (pin "1") (pinfunction "1_1") (pintype "passive"))
      (node (ref "R67") (pin "1") (pinfunction "1_1") (pintype "passive"))
      (node (ref "RESE") (pin "P1") (pinfunction "1_P1") (pintype "passive"))
      (node (ref "ST/SP") (pin "P1") (pinfunction "1_P1") (pintype "passive"))
      (node (ref "SW1") (pin "P$1") (pinfunction "P$1_P$1") (pintype "passive"))
      (node (ref "SYNC") (pin "P1") (pinfunction "1_P1") (pintype "passive"))
      (node (ref "TEMPO") (pin "2") (pinfunction "2_2") (pintype "passive"))
      (node (ref "TEMPO") (pin "4") (pinfunction "4_4") (pintype "passive"))
      (node (ref "TEMPO") (pin "GND") (pinfunction "GND_GND") (pintype "bidirectional"))
      (node (ref "U$1") (pin "4") (pinfunction "GND_4") (pintype "bidirectional"))
      (node (ref "U$2") (pin "2") (pinfunction "GND_2") (pintype "bidirectional"))
      (node (ref "U$3") (pin "3") (pinfunction "GND_3") (pintype "power_in"))
      (node (ref "U1") (pin "19") (pinfunction "TESTEN_19") (pintype "bidirectional"))
      (node (ref "U1") (pin "EPAD") (pinfunction "GND_EPAD") (pintype "bidirectional"))
      (node (ref "U2") (pin "3") (pinfunction "+IN_3") (pintype "input"))
      (node (ref "U2") (pin "4") (pinfunction "V-_4") (pintype "power_in"))
      (node (ref "U2") (pin "5") (pinfunction "+IN_5") (pintype "input"))
      (node (ref "USB") (pin "5") (pinfunction "GND_5") (pintype "bidirectional"))
      (node (ref "Y1") (pin "2") (pinfunction "GND_2") (pintype "power_in"))
      (node (ref "Y1") (pin "4") (pinfunction "GND_4") (pintype "power_in"))
    )
    (net (code "25") (name "I2C0_SCL") (class "Default")
      (node (ref "IC2") (pin "12") (pinfunction "SCL_12") (pintype "input"))
      (node (ref "U1") (pin "3") (pinfunction "GPIO1_3") (pintype "bidirectional"))
    )
    (net (code "26") (name "I2C0_SDA") (class "Default")
      (node (ref "IC2") (pin "13") (pinfunction "SDA_13") (pintype "bidirectional"))
      (node (ref "U1") (pin "2") (pinfunction "GPIO0_2") (pintype "bidirectional"))
    )
    (net (code "27") (name "I2C1_SCL") (class "Default")
      (node (ref "R24") (pin "2") (pinfunction "2_2") (pintype "passive"))
      (node (ref "U$3") (pin "10") (pinfunction "SCL_10") (pintype "bidirectional"))
    )
    (net (code "28") (name "I2C1_SDA") (class "Default")
      (node (ref "R25") (pin "2") (pinfunction "2_2") (pintype "passive"))
      (node (ref "U$3") (pin "9") (pinfunction "SDA_9") (pintype "bidirectional"))
    )
    (net (code "29") (name "LA") (class "Default")
      (node (ref "A") (pin "P$1") (pinfunction "P$1_P$1") (pintype "bidirectional"))
      (node (ref "IC2") (pin "8") (pinfunction "GPB7_8") (pintype "bidirectional"))
    )
    (net (code "30") (name "LB") (class "Default")
      (node (ref "B") (pin "P$1") (pinfunction "P$1_P$1") (pintype "bidirectional"))
      (node (ref "U1") (pin "31") (pinfunction "GPIO20_31") (pintype "bidirectional"))
    )
    (net (code "31") (name "LC") (class "Default")
      (node (ref "C") (pin "P$1") (pinfunction "P$1_P$1") (pintype "bidirectional"))
      (node (ref "U1") (pin "32") (pinfunction "GPIO21_32") (pintype "bidirectional"))
    )
    (net (code "32") (name "LD") (class "Default")
      (node (ref "D") (pin "P$1") (pinfunction "P$1_P$1") (pintype "bidirectional"))
      (node (ref "U1") (pin "34") (pinfunction "GPIO22_34") (pintype "bidirectional"))
    )
    (net (code "33") (name "LPLAY") (class "Default")
      (node (ref "IC2") (pin "7") (pinfunction "GPB6_7") (pintype "bidirectional"))
      (node (ref "PLAY") (pin "P$1") (pinfunction "P$1_P$1") (pintype "bidirectional"))
    )
    (net (code "34") (name "MEM_CLK") (class "Default")
      (node (ref "U$1") (pin "6") (pinfunction "SCK_6") (pintype "bidirectional"))
      (node (ref "U1") (pin "52") (pinfunction "QSPI_SCLK_52") (pintype "bidirectional"))
    )
    (net (code "35") (name "MEM_CS") (class "Default")
      (node (ref "R6") (pin "1") (pinfunction "1_1") (pintype "passive"))
      (node (ref "R7") (pin "1") (pinfunction "1_1") (pintype "passive"))
      (node (ref "U$1") (pin "1") (pinfunction "CS_1") (pintype "bidirectional"))
      (node (ref "U1") (pin "56") (pinfunction "QSPI_~{CS}_56") (pintype "bidirectional"))
    )
    (net (code "36") (name "MEM_I00") (class "Default")
      (node (ref "U$1") (pin "5") (pinfunction "DI_5") (pintype "bidirectional"))
      (node (ref "U1") (pin "53") (pinfunction "QSPI_SD0_53") (pintype "bidirectional"))
    )
    (net (code "37") (name "MEM_I01") (class "Default")
      (node (ref "U$1") (pin "2") (pinfunction "D0_2") (pintype "bidirectional"))
      (node (ref "U1") (pin "55") (pinfunction "QSPI_SD1_55") (pintype "bidirectional"))
    )
    (net (code "38") (name "MEM_I02") (class "Default")
      (node (ref "U$1") (pin "3") (pinfunction "I02_3") (pintype "bidirectional"))
      (node (ref "U1") (pin "54") (pinfunction "QSPI_SD2_54") (pintype "bidirectional"))
    )
    (net (code "39") (name "MEM_I03") (class "Default")
      (node (ref "U$1") (pin "7") (pinfunction "I03_7") (pintype "bidirectional"))
      (node (ref "U1") (pin "51") (pinfunction "QSPI_SD3_51") (pintype "bidirectional"))
    )
    (net (code "40") (name "MUTE") (class "Default")
      (node (ref "MUTE") (pin "1") (pinfunction "1_1") (pintype "passive"))
      (node (ref "MUTE") (pin "3") (pinfunction "3_3") (pintype "passive"))
      (node (ref "U1") (pin "16") (pinfunction "GPIO13_16") (pintype "bidirectional"))
    )
    (net (code "41") (name "NEO") (class "Default")
      (node (ref "R9") (pin "1") (pinfunction "1_1") (pintype "passive"))
      (node (ref "U1") (pin "9") (pinfunction "GPIO7_9") (pintype "bidirectional"))
    )
    (net (code "42") (name "Net-(+*--DI)") (class "Default")
      (node (ref "+*-") (pin "DIN") (pinfunction "DI_DIN") (pintype "bidirectional"))
      (node (ref "TEMPO") (pin "DOUT") (pinfunction "DO_DOUT") (pintype "bidirectional"))
    )
    (net (code "43") (name "Net-(+*--DO)") (class "Default")
      (node (ref "+*-") (pin "DOUT") (pinfunction "DO_DOUT") (pintype "bidirectional"))
      (node (ref "MUTE") (pin "DIN") (pinfunction "DI_DIN") (pintype "bidirectional"))
    )
    (net (code "44") (name "Net-(A-PadP$2)") (class "Default")
      (node (ref "A") (pin "P$2") (pinfunction "P$2_P$2") (pintype "bidirectional"))
      (node (ref "R12") (pin "1") (pinfunction "1_1") (pintype "passive"))
    )
    (net (code "45") (name "Net-(ALT-DI)") (class "Default")
      (node (ref "ALT") (pin "DIN") (pinfunction "DI_DIN") (pintype "bidirectional"))
      (node (ref "R9") (pin "2") (pinfunction "2_2") (pintype "passive"))
    )
    (net (code "46") (name "Net-(ALT-DO)") (class "Default")
      (node (ref "ALT") (pin "DOUT") (pinfunction "DO_DOUT") (pintype "bidirectional"))
      (node (ref "CV") (pin "DIN") (pinfunction "DI_DIN") (pintype "bidirectional"))
    )
    (net (code "47") (name "Net-(A_CV-3)") (class "Default")
      (node (ref "A_CV") (pin "P3") (pinfunction "3_P3") (pintype "passive"))
      (node (ref "R8") (pin "2") (pinfunction "2_2") (pintype "passive"))
    )
    (net (code "48") (name "Net-(A_OUT-3)") (class "Default")
      (node (ref "A_OUT") (pin "P3") (pinfunction "3_P3") (pintype "passive"))
      (node (ref "R17") (pin "2") (pinfunction "2_2") (pintype "passive"))
    )
    (net (code "49") (name "Net-(B-PadP$2)") (class "Default")
      (node (ref "B") (pin "P$2") (pinfunction "P$2_P$2") (pintype "bidirectional"))
      (node (ref "R13") (pin "1") (pinfunction "1_1") (pintype "passive"))
    )
    (net (code "50") (name "Net-(BAR-C)") (class "Default")
      (node (ref "BAR") (pin "K") (pinfunction "C_K") (pintype "passive"))
      (node (ref "IC2") (pin "5") (pinfunction "GPB4_5") (pintype "bidirectional"))
    )
    (net (code "51") (name "Net-(BAR-PadA)") (class "Default")
      (node (ref "BAR") (pin "A") (pinfunction "A_A") (pintype "passive"))
      (node (ref "R70") (pin "2") (pinfunction "2_2") (pintype "passive"))
    )
    (net (code "52") (name "Net-(BEAT-C)") (class "Default")
      (node (ref "BEAT") (pin "K") (pinfunction "C_K") (pintype "passive"))
      (node (ref "IC2") (pin "6") (pinfunction "GPB5_6") (pintype "bidirectional"))
    )
    (net (code "53") (name "Net-(BEAT-PadA)") (class "Default")
      (node (ref "BEAT") (pin "A") (pinfunction "A_A") (pintype "passive"))
      (node (ref "R21") (pin "2") (pinfunction "2_2") (pintype "passive"))
    )
    (net (code "54") (name "Net-(B_CV-3)") (class "Default")
      (node (ref "B_CV") (pin "P3") (pinfunction "3_P3") (pintype "passive"))
      (node (ref "R27") (pin "2") (pinfunction "2_2") (pintype "passive"))
    )
    (net (code "55") (name "Net-(B_OUT-3)") (class "Default")
      (node (ref "B_OUT") (pin "P3") (pinfunction "3_P3") (pintype "passive"))
      (node (ref "R43") (pin "2") (pinfunction "2_2") (pintype "passive"))
    )
    (net (code "56") (name "Net-(C-PadP$2)") (class "Default")
      (node (ref "C") (pin "P$2") (pinfunction "P$2_P$2") (pintype "bidirectional"))
      (node (ref "R14") (pin "1") (pinfunction "1_1") (pintype "passive"))
    )
    (net (code "57") (name "Net-(C3-Pad1)") (class "Default")
      (node (ref "C3") (pin "1") (pinfunction "1_1") (pintype "passive"))
      (node (ref "L2") (pin "2") (pinfunction "2_2") (pintype "passive"))
      (node (ref "L3") (pin "1") (pinfunction "1_1") (pintype "passive"))
    )
    (net (code "58") (name "Net-(C10-Pad2)") (class "Default")
      (node (ref "C10") (pin "2") (pinfunction "2_2") (pintype "passive"))
      (node (ref "C9") (pin "2") (pinfunction "2_2") (pintype "passive"))
      (node (ref "L1") (pin "2") (pinfunction "2_2") (pintype "passive"))
      (node (ref "L4") (pin "1") (pinfunction "1_1") (pintype "passive"))
      (node (ref "R3") (pin "1") (pinfunction "1_1") (pintype "passive"))
    )
    (net (code "59") (name "Net-(C14-Pad2)") (class "Default")
      (node (ref "C14") (pin "2") (pinfunction "2_2") (pintype "passive"))
      (node (ref "C15") (pin "2") (pinfunction "2_2") (pintype "passive"))
      (node (ref "U1") (pin "23") (pinfunction "VDD_1V1_23") (pintype "bidirectional"))
      (node (ref "U1") (pin "50") (pinfunction "VDD_1V1_50") (pintype "bidirectional"))
    )
    (net (code "60") (name "Net-(C16-Pad1)") (class "Default")
      (node (ref "C16") (pin "1") (pinfunction "1_1") (pintype "passive"))
      (node (ref "R5") (pin "2") (pinfunction "2_2") (pintype "passive"))
      (node (ref "USB") (pin "G") (pinfunction "SHIELD_G") (pintype "bidirectional"))
      (node (ref "USB") (pin "G2") (pinfunction "SHIELD_G2") (pintype "bidirectional"))
      (node (ref "USB") (pin "G3") (pinfunction "SHIELD_G3") (pintype "bidirectional"))
      (node (ref "USB") (pin "G4") (pinfunction "SHIELD_G4") (pintype "bidirectional"))
    )
    (net (code "61") (name "Net-(CHANCE-DI)") (class "Default")
      (node (ref "CHANCE") (pin "DIN") (pinfunction "DI_DIN") (pintype "bidirectional"))
      (node (ref "CV") (pin "DOUT") (pinfunction "DO_DOUT") (pintype "bidirectional"))
    )
    (net (code "62") (name "Net-(CHANCE-DO)") (class "Default")
      (node (ref "CHANCE") (pin "DOUT") (pinfunction "DO_DOUT") (pintype "bidirectional"))
      (node (ref "TEMPO") (pin "DIN") (pinfunction "DI_DIN") (pintype "bidirectional"))
    )
    (net (code "63") (name "Net-(C_CV-3)") (class "Default")
      (node (ref "C_CV") (pin "P3") (pinfunction "3_P3") (pintype "passive"))
      (node (ref "R26") (pin "2") (pinfunction "2_2") (pintype "passive"))
    )
    (net (code "64") (name "Net-(C_OUT-3)") (class "Default")
      (node (ref "C_OUT") (pin "P3") (pinfunction "3_P3") (pintype "passive"))
      (node (ref "R47") (pin "2") (pinfunction "2_2") (pintype "passive"))
    )
    (net (code "65") (name "Net-(D-PadP$2)") (class "Default")
      (node (ref "D") (pin "P$2") (pinfunction "P$2_P$2") (pintype "bidirectional"))
      (node (ref "R15") (pin "1") (pinfunction "1_1") (pintype "passive"))
    )
    (net (code "66") (name "Net-(D21-PadA)") (class "Default")
      (node (ref "D21") (pin "A") (pinfunction "A_A") (pintype "passive"))
      (node (ref "F1") (pin "1") (pinfunction "1_1") (pintype "passive"))
    )
    (net (code "67") (name "Net-(D30-PadC)") (class "Default")
      (node (ref "D30") (pin "C") (pinfunction "C_C") (pintype "passive"))
      (node (ref "F2") (pin "1") (pinfunction "1_1") (pintype "passive"))
    )
    (net (code "68") (name "Net-(D_CV-3)") (class "Default")
      (node (ref "D_CV") (pin "P3") (pinfunction "3_P3") (pintype "passive"))
      (node (ref "R30") (pin "2") (pinfunction "2_2") (pintype "passive"))
    )
    (net (code "69") (name "Net-(D_OUT-3)") (class "Default")
      (node (ref "D_OUT") (pin "P3") (pinfunction "3_P3") (pintype "passive"))
      (node (ref "R51") (pin "2") (pinfunction "2_2") (pintype "passive"))
    )
    (net (code "70") (name "Net-(ENCODER-PadA)") (class "Default")
      (node (ref "ENCODER") (pin "A") (pinfunction "A_A") (pintype "passive"))
      (node (ref "R20") (pin "1") (pinfunction "1_1") (pintype "passive"))
      (node (ref "R39") (pin "2") (pinfunction "2_2") (pintype "passive"))
    )
    (net (code "71") (name "Net-(ENCODERA-B)") (class "Default")
      (node (ref "ENCODER") (pin "C") (pinfunction "B_C") (pintype "passive"))
      (node (ref "R37") (pin "2") (pinfunction "2_2") (pintype "passive"))
      (node (ref "R38") (pin "2") (pinfunction "2_2") (pintype "passive"))
    )
    (net (code "72") (name "Net-(F1-Pad2)") (class "Default")
      (node (ref "F1") (pin "2") (pinfunction "2_2") (pintype "passive"))
      (node (ref "POWER") (pin "10") (pinfunction "10_10") (pintype "passive"))
      (node (ref "POWER") (pin "9") (pinfunction "9_9") (pintype "passive"))
    )
    (net (code "73") (name "Net-(F2-Pad2)") (class "Default")
      (node (ref "F2") (pin "2") (pinfunction "2_2") (pintype "passive"))
      (node (ref "POWER") (pin "1") (pinfunction "1_1") (pintype "passive"))
      (node (ref "POWER") (pin "2") (pinfunction "2_2") (pintype "passive"))
    )
    (net (code "74") (name "Net-(IC2-GPA0)") (class "Default")
      (node (ref "IC2") (pin "21") (pinfunction "GPA0_21") (pintype "bidirectional"))
      (node (ref "LFD36BUE-101B") (pin "11") (pinfunction "A_11") (pintype "bidirectional"))
    )
    (net (code "75") (name "Net-(IC2-GPA1)") (class "Default")
      (node (ref "IC2") (pin "22") (pinfunction "GPA1_22") (pintype "bidirectional"))
      (node (ref "LFD36BUE-101B") (pin "7") (pinfunction "B_7") (pintype "bidirectional"))
    )
    (net (code "76") (name "Net-(IC2-GPA2)") (class "Default")
      (node (ref "IC2") (pin "23") (pinfunction "GPA2_23") (pintype "bidirectional"))
      (node (ref "LFD36BUE-101B") (pin "4") (pinfunction "C_4") (pintype "bidirectional"))
    )
    (net (code "77") (name "Net-(IC2-GPA3)") (class "Default")
      (node (ref "IC2") (pin "24") (pinfunction "GPA3_24") (pintype "bidirectional"))
      (node (ref "LFD36BUE-101B") (pin "2") (pinfunction "D_2") (pintype "bidirectional"))
    )
    (net (code "78") (name "Net-(IC2-GPA4)") (class "Default")
      (node (ref "IC2") (pin "25") (pinfunction "GPA4_25") (pintype "bidirectional"))
      (node (ref "LFD36BUE-101B") (pin "1") (pinfunction "E_1") (pintype "bidirectional"))
    )
    (net (code "79") (name "Net-(IC2-GPA5)") (class "Default")
      (node (ref "IC2") (pin "26") (pinfunction "GPA5_26") (pintype "bidirectional"))
      (node (ref "LFD36BUE-101B") (pin "10") (pinfunction "F_10") (pintype "bidirectional"))
    )
    (net (code "80") (name "Net-(IC2-GPA6)") (class "Default")
      (node (ref "IC2") (pin "27") (pinfunction "GPA6_27") (pintype "bidirectional"))
      (node (ref "LFD36BUE-101B") (pin "5") (pinfunction "G_5") (pintype "bidirectional"))
    )
    (net (code "81") (name "Net-(IC2-GPA7)") (class "Default")
      (node (ref "IC2") (pin "28") (pinfunction "GPA7_28") (pintype "bidirectional"))
      (node (ref "LFD36BUE-101B") (pin "3") (pinfunction "DP_3") (pintype "bidirectional"))
    )
    (net (code "82") (name "Net-(IC2-GPB0)") (class "Default")
      (node (ref "IC2") (pin "1") (pinfunction "GPB0_1") (pintype "bidirectional"))
      (node (ref "LFD36BUE-101B") (pin "12") (pinfunction "D1_12") (pintype "bidirectional"))
    )
    (net (code "83") (name "Net-(IC2-GPB1)") (class "Default")
      (node (ref "IC2") (pin "2") (pinfunction "GPB1_2") (pintype "bidirectional"))
      (node (ref "LFD36BUE-101B") (pin "9") (pinfunction "D2_9") (pintype "bidirectional"))
    )
    (net (code "84") (name "Net-(IC2-GPB2)") (class "Default")
      (node (ref "IC2") (pin "3") (pinfunction "GPB2_3") (pintype "bidirectional"))
      (node (ref "LFD36BUE-101B") (pin "8") (pinfunction "D3_8") (pintype "bidirectional"))
    )
    (net (code "85") (name "Net-(IC2-GPB3)") (class "Default")
      (node (ref "IC2") (pin "4") (pinfunction "GPB3_4") (pintype "bidirectional"))
      (node (ref "LFD36BUE-101B") (pin "6") (pinfunction "D4_6") (pintype "bidirectional"))
    )
    (net (code "86") (name "Net-(IC3A--IN)") (class "Default")
      (node (ref "C37") (pin "1") (pinfunction "1_1") (pintype "passive"))
      (node (ref "IC3") (pin "2") (pinfunction "-IN_2") (pintype "input"))
      (node (ref "R27") (pin "1") (pinfunction "1_1") (pintype "passive"))
      (node (ref "R28") (pin "2") (pinfunction "2_2") (pintype "passive"))
    )
    (net (code "87") (name "Net-(IC3B--IN)") (class "Default")
      (node (ref "C36") (pin "1") (pinfunction "1_1") (pintype "passive"))
      (node (ref "IC3") (pin "6") (pinfunction "-IN_6") (pintype "input"))
      (node (ref "R10") (pin "2") (pinfunction "2_2") (pintype "passive"))
      (node (ref "R8") (pin "1") (pinfunction "1_1") (pintype "passive"))
    )
    (net (code "88") (name "Net-(IC3C--IN)") (class "Default")
      (node (ref "C38") (pin "1") (pinfunction "1_1") (pintype "passive"))
      (node (ref "IC3") (pin "9") (pinfunction "-IN_9") (pintype "input"))
      (node (ref "R26") (pin "1") (pinfunction "1_1") (pintype "passive"))
      (node (ref "R29") (pin "2") (pinfunction "2_2") (pintype "passive"))
    )
    (net (code "89") (name "Net-(IC3D--IN)") (class "Default")
      (node (ref "C39") (pin "1") (pinfunction "1_1") (pintype "passive"))
      (node (ref "IC3") (pin "13") (pinfunction "-IN_13") (pintype "input"))
      (node (ref "R30") (pin "1") (pinfunction "1_1") (pintype "passive"))
      (node (ref "R31") (pin "2") (pinfunction "2_2") (pintype "passive"))
    )
    (net (code "90") (name "Net-(LED_A_OUT-PadA)") (class "Default")
      (node (ref "LED_A_OUT") (pin "A") (pinfunction "A_A") (pintype "passive"))
      (node (ref "R19") (pin "2") (pinfunction "2_2") (pintype "passive"))
    )
    (net (code "91") (name "Net-(LED_B_OUT-PadA)") (class "Default")
      (node (ref "LED_B_OUT") (pin "A") (pinfunction "A_A") (pintype "passive"))
      (node (ref "R45") (pin "2") (pinfunction "2_2") (pintype "passive"))
    )
    (net (code "92") (name "Net-(LED_C_OUT-PadA)") (class "Default")
      (node (ref "LED_C_OUT") (pin "A") (pinfunction "A_A") (pintype "passive"))
      (node (ref "R49") (pin "2") (pinfunction "2_2") (pintype "passive"))
    )
    (net (code "93") (name "Net-(LED_D_OUT-PadA)") (class "Default")
      (node (ref "LED_D_OUT") (pin "A") (pinfunction "A_A") (pintype "passive"))
      (node (ref "R53") (pin "2") (pinfunction "2_2") (pintype "passive"))
    )
    (net (code "94") (name "Net-(MUTE-DO)") (class "Default")
      (node (ref "MUTE") (pin "DOUT") (pinfunction "DO_DOUT") (pintype "bidirectional"))
      (node (ref "PRESET") (pin "DIN") (pinfunction "DI_DIN") (pintype "bidirectional"))
    )
    (net (code "95") (name "Net-(PLAY-PadP$2)") (class "Default")
      (node (ref "PLAY") (pin "P$2") (pinfunction "P$2_P$2") (pintype "bidirectional"))
      (node (ref "R11") (pin "1") (pinfunction "1_1") (pintype "passive"))
    )
    (net (code "96") (name "Net-(PRESE-3)") (class "Default")
      (node (ref "PRESE") (pin "P3") (pinfunction "3_P3") (pintype "passive"))
      (node (ref "R34") (pin "2") (pinfunction "2_2") (pintype "passive"))
    )
    (net (code "97") (name "Net-(Q1-B)") (class "Default")
      (node (ref "Q1") (pin "1") (pinfunction "B_1") (pintype "passive"))
      (node (ref "R33") (pin "2") (pinfunction "2_2") (pintype "passive"))
      (node (ref "R36") (pin "1") (pinfunction "1_1") (pintype "passive"))
    )
    (net (code "98") (name "Net-(Q2-B)") (class "Default")
      (node (ref "Q2") (pin "1") (pinfunction "B_1") (pintype "passive"))
      (node (ref "R58") (pin "1") (pinfunction "1_1") (pintype "passive"))
    )
    (net (code "99") (name "Net-(Q2-C)") (class "Default")
      (node (ref "Q2") (pin "3") (pinfunction "C_3") (pintype "passive"))
      (node (ref "R42") (pin "1") (pinfunction "1_1") (pintype "passive"))
      (node (ref "R57") (pin "2") (pinfunction "2_2") (pintype "passive"))
    )
    (net (code "100") (name "Net-(Q3-B)") (class "Default")
      (node (ref "Q3") (pin "1") (pinfunction "B_1") (pintype "passive"))
      (node (ref "R32") (pin "1") (pinfunction "1_1") (pintype "passive"))
      (node (ref "R67") (pin "2") (pinfunction "2_2") (pintype "passive"))
    )
    (net (code "101") (name "Net-(Q4-B)") (class "Default")
      (node (ref "Q4") (pin "1") (pinfunction "B_1") (pintype "passive"))
      (node (ref "R16") (pin "1") (pinfunction "1_1") (pintype "passive"))
    )
    (net (code "102") (name "Net-(Q4-C)") (class "Default")
      (node (ref "Q4") (pin "3") (pinfunction "C_3") (pintype "passive"))
      (node (ref "R17") (pin "1") (pinfunction "1_1") (pintype "passive"))
      (node (ref "R18") (pin "2") (pinfunction "2_2") (pintype "passive"))
    )
    (net (code "103") (name "Net-(Q5-B)") (class "Default")
      (node (ref "Q5") (pin "1") (pinfunction "B_1") (pintype "passive"))
      (node (ref "R40") (pin "1") (pinfunction "1_1") (pintype "passive"))
    )
    (net (code "104") (name "Net-(Q5-C)") (class "Default")
      (node (ref "Q5") (pin "3") (pinfunction "C_3") (pintype "passive"))
      (node (ref "R43") (pin "1") (pinfunction "1_1") (pintype "passive"))
      (node (ref "R44") (pin "2") (pinfunction "2_2") (pintype "passive"))
    )
    (net (code "105") (name "Net-(Q6-B)") (class "Default")
      (node (ref "Q6") (pin "1") (pinfunction "B_1") (pintype "passive"))
      (node (ref "R46") (pin "1") (pinfunction "1_1") (pintype "passive"))
    )
    (net (code "106") (name "Net-(Q6-C)") (class "Default")
      (node (ref "Q6") (pin "3") (pinfunction "C_3") (pintype "passive"))
      (node (ref "R47") (pin "1") (pinfunction "1_1") (pintype "passive"))
      (node (ref "R48") (pin "2") (pinfunction "2_2") (pintype "passive"))
    )
    (net (code "107") (name "Net-(Q7-B)") (class "Default")
      (node (ref "Q7") (pin "1") (pinfunction "B_1") (pintype "passive"))
      (node (ref "R50") (pin "1") (pinfunction "1_1") (pintype "passive"))
    )
    (net (code "108") (name "Net-(Q7-C)") (class "Default")
      (node (ref "Q7") (pin "3") (pinfunction "C_3") (pintype "passive"))
      (node (ref "R51") (pin "1") (pinfunction "1_1") (pintype "passive"))
      (node (ref "R52") (pin "2") (pinfunction "2_2") (pintype "passive"))
    )
    (net (code "109") (name "Net-(R7-Pad2)") (class "Default")
      (node (ref "R7") (pin "2") (pinfunction "2_2") (pintype "passive"))
      (node (ref "SW1") (pin "P$2") (pinfunction "P$2_P$2") (pintype "passive"))
    )
    (net (code "110") (name "Net-(RESE-3)") (class "Default")
      (node (ref "R36") (pin "2") (pinfunction "2_2") (pintype "passive"))
      (node (ref "RESE") (pin "P3") (pinfunction "3_P3") (pintype "passive"))
    )
    (net (code "111") (name "Net-(ST/SP-3)") (class "Default")
      (node (ref "R42") (pin "2") (pinfunction "2_2") (pintype "passive"))
      (node (ref "ST/SP") (pin "P3") (pinfunction "3_P3") (pintype "passive"))
    )
    (net (code "112") (name "Net-(SYNC-3)") (class "Default")
      (node (ref "R32") (pin "2") (pinfunction "2_2") (pintype "passive"))
      (node (ref "SYNC") (pin "P3") (pinfunction "3_P3") (pintype "passive"))
    )
    (net (code "113") (name "Net-(U$2-BST)") (class "Default")
      (node (ref "C8") (pin "2") (pinfunction "2_2") (pintype "passive"))
      (node (ref "U$2") (pin "1") (pinfunction "BST_1") (pintype "bidirectional"))
    )
    (net (code "114") (name "Net-(U$2-EN)") (class "Default")
      (node (ref "R1") (pin "2") (pinfunction "2_2") (pintype "passive"))
      (node (ref "U$2") (pin "4") (pinfunction "EN_4") (pintype "power_in"))
    )
    (net (code "115") (name "Net-(U$2-FB)") (class "Default")
      (node (ref "C9") (pin "1") (pinfunction "1_1") (pintype "passive"))
      (node (ref "R2") (pin "2") (pinfunction "2_2") (pintype "passive"))
      (node (ref "R3") (pin "2") (pinfunction "2_2") (pintype "passive"))
      (node (ref "U$2") (pin "3") (pinfunction "FB_3") (pintype "bidirectional"))
    )
    (net (code "116") (name "Net-(U$2-SW)") (class "Default")
      (node (ref "C8") (pin "1") (pinfunction "1_1") (pintype "passive"))
      (node (ref "D1") (pin "C") (pinfunction "C_C") (pintype "passive"))
      (node (ref "L1") (pin "1") (pinfunction "1_1") (pintype "passive"))
      (node (ref "U$2") (pin "6") (pinfunction "SW_6") (pintype "power_in"))
    )
    (net (code "117") (name "Net-(U$2-VIN)") (class "Default")
      (node (ref "C5") (pin "1") (pinfunction "1_1") (pintype "passive"))
      (node (ref "C6") (pin "1") (pinfunction "1_1") (pintype "passive"))
      (node (ref "C7") (pin "1") (pinfunction "1_1") (pintype "passive"))
      (node (ref "L3") (pin "2") (pinfunction "2_2") (pintype "passive"))
      (node (ref "R1") (pin "1") (pinfunction "1_1") (pintype "passive"))
      (node (ref "U$2") (pin "5") (pinfunction "VIN_5") (pintype "bidirectional"))
    )
    (net (code "118") (name "Net-(U$3-ADDR)") (class "Default")
      (node (ref "R22") (pin "1") (pinfunction "1_1") (pintype "passive"))
      (node (ref "U$3") (pin "1") (pinfunction "ADDR_1") (pintype "bidirectional"))
    )
    (net (code "119") (name "Net-(U$3-ALRT)") (class "Default")
      (node (ref "R23") (pin "2") (pinfunction "2_2") (pintype "passive"))
      (node (ref "U$3") (pin "2") (pinfunction "ALRT_2") (pintype "bidirectional"))
    )
    (net (code "120") (name "Net-(U1-LDO_OUT)") (class "Default")
      (node (ref "C12") (pin "1") (pinfunction "1_1") (pintype "passive"))
      (node (ref "U1") (pin "45") (pinfunction "LDO_OUT_45") (pintype "bidirectional"))
    )
    (net (code "121") (name "Net-(U1-USB_D+)") (class "Default")
      (node (ref "R55") (pin "2") (pinfunction "2_2") (pintype "passive"))
      (node (ref "U1") (pin "47") (pinfunction "USB_D+_47") (pintype "bidirectional"))
    )
    (net (code "122") (name "Net-(U1-USB_D-)") (class "Default")
      (node (ref "R54") (pin "1") (pinfunction "1_1") (pintype "passive"))
      (node (ref "U1") (pin "46") (pinfunction "USB_D-_46") (pintype "bidirectional"))
    )
    (net (code "123") (name "Net-(U1-XIN)") (class "Default")
      (node (ref "C4") (pin "2") (pinfunction "2_2") (pintype "passive"))
      (node (ref "U1") (pin "20") (pinfunction "XIN_20") (pintype "bidirectional"))
      (node (ref "Y1") (pin "1") (pinfunction "1_1") (pintype "passive"))
    )
    (net (code "124") (name "Net-(U1-XOUT)") (class "Default")
      (node (ref "R109") (pin "2") (pinfunction "2_2") (pintype "passive"))
      (node (ref "U1") (pin "21") (pinfunction "XOUT_21") (pintype "bidirectional"))
    )
    (net (code "125") (name "Net-(U2A--IN)") (class "Default")
      (node (ref "C41") (pin "1") (pinfunction "1_1") (pintype "passive"))
      (node (ref "R34") (pin "1") (pinfunction "1_1") (pintype "passive"))
      (node (ref "R35") (pin "2") (pinfunction "2_2") (pintype "passive"))
      (node (ref "U2") (pin "2") (pinfunction "-IN_2") (pintype "input"))
    )
    (net (code "126") (name "Net-(U2B--IN)") (class "Default")
      (node (ref "U2") (pin "6") (pinfunction "-IN_6") (pintype "input"))
      (node (ref "U2") (pin "7") (pinfunction "OUT_7") (pintype "output"))
    )
    (net (code "127") (name "Net-(USB-D+)") (class "Default")
      (node (ref "R55") (pin "1") (pinfunction "1_1") (pintype "passive"))
      (node (ref "USB") (pin "3") (pinfunction "D+_3") (pintype "bidirectional"))
    )
    (net (code "128") (name "Net-(USB-D-)") (class "Default")
      (node (ref "R54") (pin "2") (pinfunction "2_2") (pintype "passive"))
      (node (ref "USB") (pin "2") (pinfunction "D-_2") (pintype "bidirectional"))
    )
    (net (code "129") (name "Net-(Y1-2)") (class "Default")
      (node (ref "C1") (pin "1") (pinfunction "1_1") (pintype "passive"))
      (node (ref "R109") (pin "1") (pinfunction "1_1") (pintype "passive"))
      (node (ref "Y1") (pin "3") (pinfunction "2_3") (pintype "passive"))
    )
    (net (code "130") (name "PLAY") (class "Default")
      (node (ref "PLAY") (pin "3") (pinfunction "3_3") (pintype "passive"))
      (node (ref "PLAY") (pin "4") (pinfunction "4_4") (pintype "passive"))
      (node (ref "U1") (pin "30") (pinfunction "GPIO19_30") (pintype "bidirectional"))
    )
    (net (code "131") (name "PRESE_CV") (class "Default")
      (node (ref "C41") (pin "2") (pinfunction "2_2") (pintype "passive"))
      (node (ref "R35") (pin "1") (pinfunction "1_1") (pintype "passive"))
      (node (ref "U1") (pin "41") (pinfunction "GPIO29/ADC3_41") (pintype "bidirectional"))
      (node (ref "U2") (pin "1") (pinfunction "OUT_1") (pintype "output"))
    )
    (net (code "132") (name "PREST") (class "Default")
      (node (ref "PRESET") (pin "1") (pinfunction "1_1") (pintype "passive"))
      (node (ref "PRESET") (pin "3") (pinfunction "3_3") (pintype "passive"))
      (node (ref "U1") (pin "17") (pinfunction "GPIO14_17") (pintype "bidirectional"))
    )
    (net (code "133") (name "RESE_CV") (class "Default")
      (node (ref "Q1") (pin "3") (pinfunction "C_3") (pintype "passive"))
      (node (ref "R41") (pin "1") (pinfunction "1_1") (pintype "passive"))
      (node (ref "U1") (pin "8") (pinfunction "GPIO6_8") (pintype "bidirectional"))
    )
    (net (code "134") (name "RUN") (class "Default")
      (node (ref "PL1") (pin "10") (pinfunction "10_10") (pintype "passive"))
      (node (ref "R4") (pin "2") (pinfunction "2_2") (pintype "passive"))
      (node (ref "U1") (pin "26") (pinfunction "RUN_26") (pintype "bidirectional"))
    )
    (net (code "135") (name "ST{slash}SP") (class "Default")
      (node (ref "R58") (pin "2") (pinfunction "2_2") (pintype "passive"))
      (node (ref "U1") (pin "35") (pinfunction "GPIO23_35") (pintype "bidirectional"))
    )
    (net (code "136") (name "SWCLK") (class "Default")
      (node (ref "JP1") (pin "2") (pinfunction "2_2") (pintype "passive"))
      (node (ref "PL1") (pin "4") (pinfunction "4_4") (pintype "passive"))
      (node (ref "U1") (pin "24") (pinfunction "SWCLK_24") (pintype "bidirectional"))
    )
    (net (code "137") (name "SWDI0") (class "Default")
      (node (ref "JP1") (pin "3") (pinfunction "3_3") (pintype "passive"))
      (node (ref "PL1") (pin "2") (pinfunction "2_2") (pintype "passive"))
      (node (ref "U1") (pin "25") (pinfunction "SWDIO_25") (pintype "bidirectional"))
    )
    (net (code "138") (name "SYNC_CV") (class "Default")
      (node (ref "Q3") (pin "3") (pinfunction "C_3") (pintype "passive"))
      (node (ref "R72") (pin "1") (pinfunction "1_1") (pintype "passive"))
      (node (ref "U1") (pin "7") (pinfunction "GPIO5_7") (pintype "bidirectional"))
    )
    (net (code "139") (name "TEMP") (class "Default")
      (node (ref "TEMPO") (pin "1") (pinfunction "1_1") (pintype "passive"))
      (node (ref "TEMPO") (pin "3") (pinfunction "3_3") (pintype "passive"))
      (node (ref "U1") (pin "14") (pinfunction "GPIO11_14") (pintype "bidirectional"))
    )
    (net (code "140") (name "unconnected-(A_OUT-2-PadP2)") (class "Default")
      (node (ref "A_OUT") (pin "P2") (pinfunction "2_P2") (pintype "passive"))
    )
    (net (code "141") (name "unconnected-(B_OUT-2-PadP2)") (class "Default")
      (node (ref "B_OUT") (pin "P2") (pinfunction "2_P2") (pintype "passive"))
    )
    (net (code "142") (name "unconnected-(C_OUT-2-PadP2)") (class "Default")
      (node (ref "C_OUT") (pin "P2") (pinfunction "2_P2") (pintype "passive"))
    )
    (net (code "143") (name "unconnected-(D_OUT-2-PadP2)") (class "Default")
      (node (ref "D_OUT") (pin "P2") (pinfunction "2_P2") (pintype "passive"))
    )
    (net (code "144") (name "unconnected-(IC2-INTA-Pad20)") (class "Default")
      (node (ref "IC2") (pin "20") (pinfunction "INTA_20") (pintype "output"))
    )
    (net (code "145") (name "unconnected-(IC2-INTB-Pad19)") (class "Default")
      (node (ref "IC2") (pin "19") (pinfunction "INTB_19") (pintype "output"))
    )
    (net (code "146") (name "unconnected-(PL1-Pad6)") (class "Default")
      (node (ref "PL1") (pin "6") (pinfunction "6_6") (pintype "passive"))
    )
    (net (code "147") (name "unconnected-(PL1-Pad7)") (class "Default")
      (node (ref "PL1") (pin "7") (pinfunction "7_7") (pintype "passive"))
    )
    (net (code "148") (name "unconnected-(PL1-Pad8)") (class "Default")
      (node (ref "PL1") (pin "8") (pinfunction "8_8") (pintype "passive"))
    )
    (net (code "149") (name "unconnected-(PRESET-DO-PadDOUT)") (class "Default")
      (node (ref "PRESET") (pin "DOUT") (pinfunction "DO_DOUT") (pintype "bidirectional"))
    )
    (net (code "150") (name "unconnected-(RESE-2-PadP2)") (class "Default")
      (node (ref "RESE") (pin "P2") (pinfunction "2_P2") (pintype "passive"))
    )
    (net (code "151") (name "unconnected-(ST/SP-2-PadP2)") (class "Default")
      (node (ref "ST/SP") (pin "P2") (pinfunction "2_P2") (pintype "passive"))
    )
    (net (code "152") (name "unconnected-(SYNC-2-PadP2)") (class "Default")
      (node (ref "SYNC") (pin "P2") (pinfunction "2_P2") (pintype "passive"))
    )
    (net (code "153") (name "unconnected-(U1-GPIO28{slash}ADC2-Pad40)") (class "Default")
      (node (ref "U1") (pin "40") (pinfunction "GPIO28/ADC2_40") (pintype "bidirectional"))
    )
    (net (code "154") (name "unconnected-(USB-ID-Pad4)") (class "Default")
      (node (ref "USB") (pin "4") (pinfunction "ID_4") (pintype "bidirectional"))
    )
    (net (code "155") (name "unconnected-(USB-VCC-Pad1)") (class "Default")
      (node (ref "USB") (pin "1") (pinfunction "VCC_1") (pintype "bidirectional"))
    )
  )
)
